# rev_p_v17.net
KiCad netlist of a schematic drawn in EAGLE
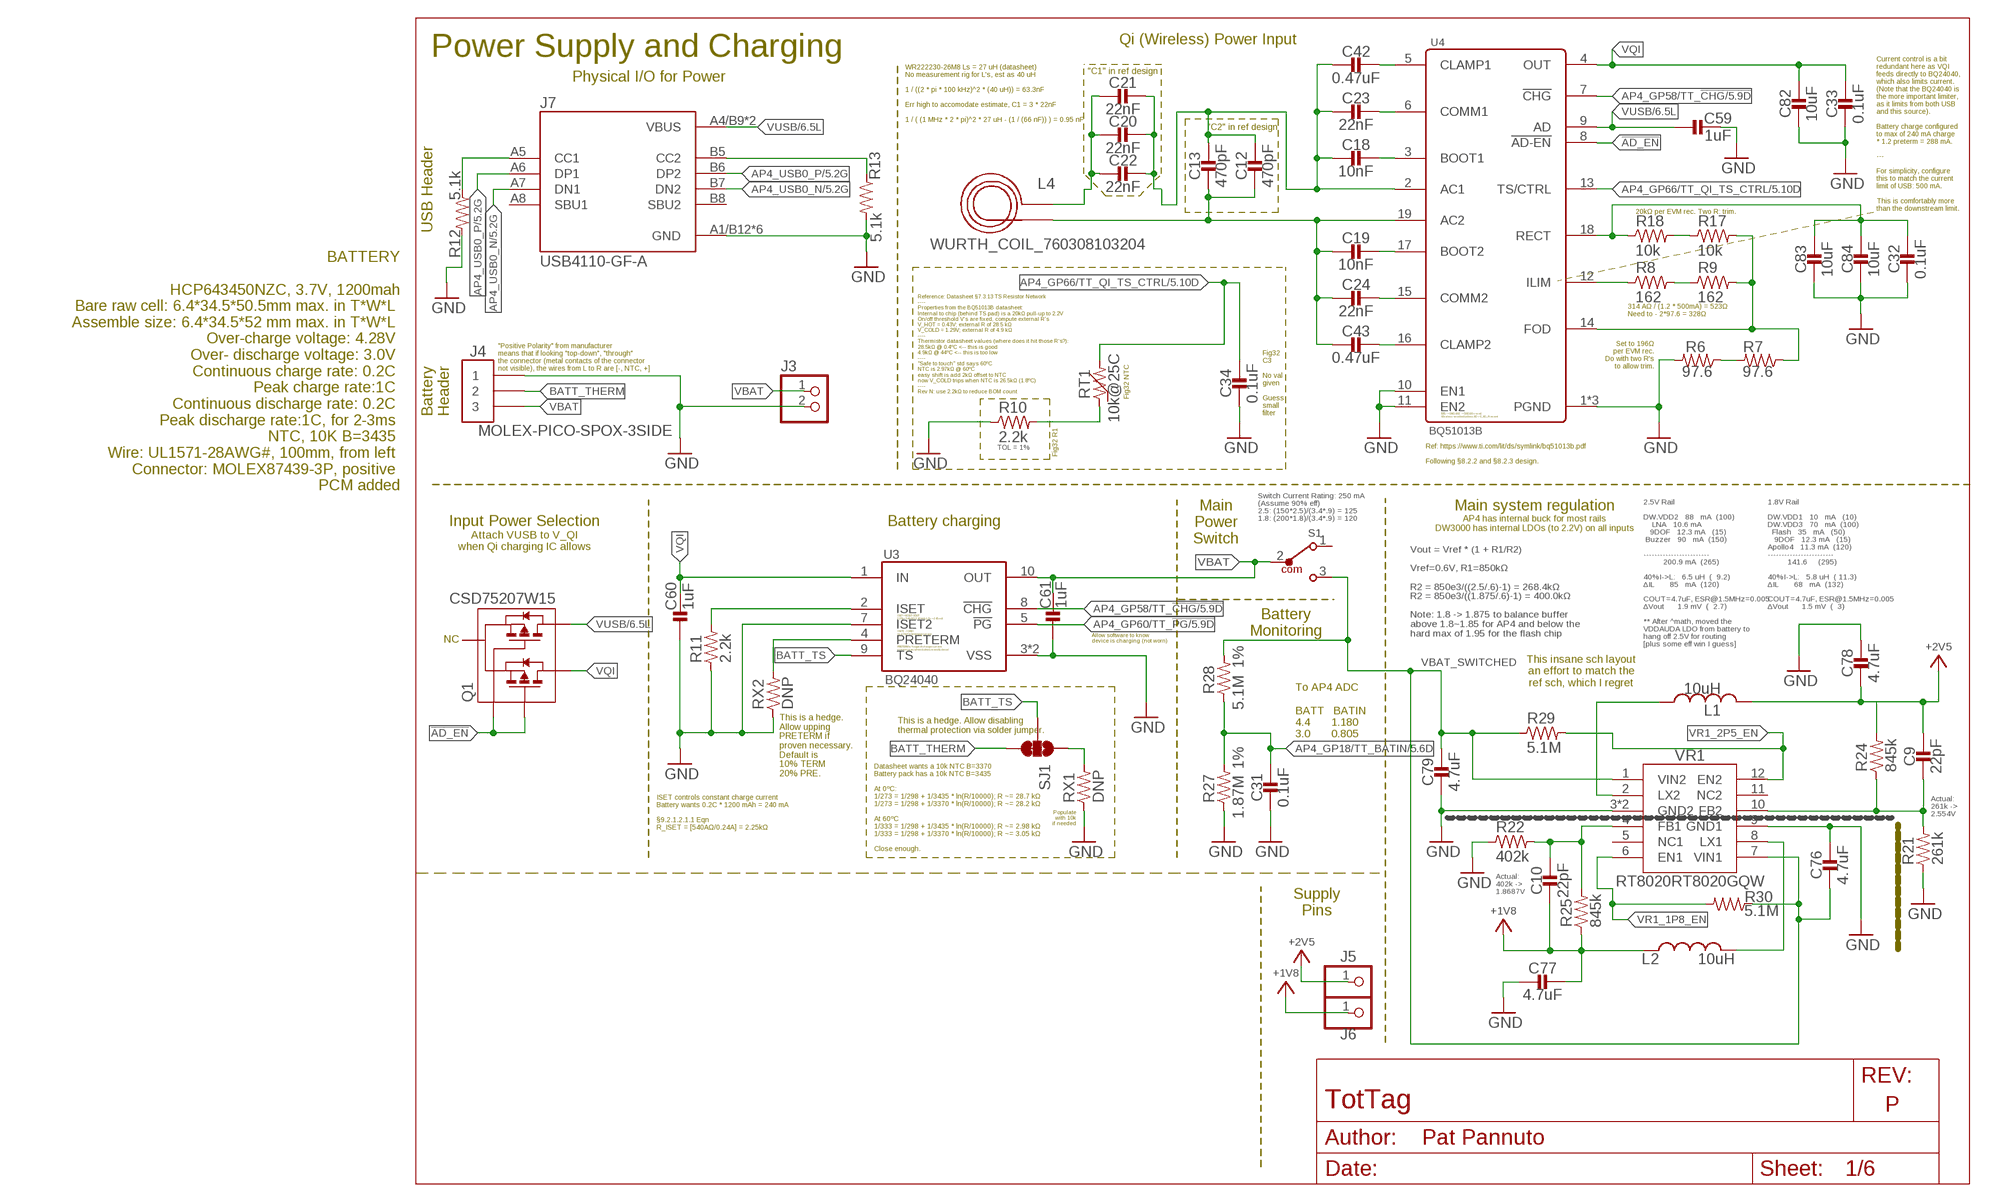
[diagram p0: schematic, sheet 1]
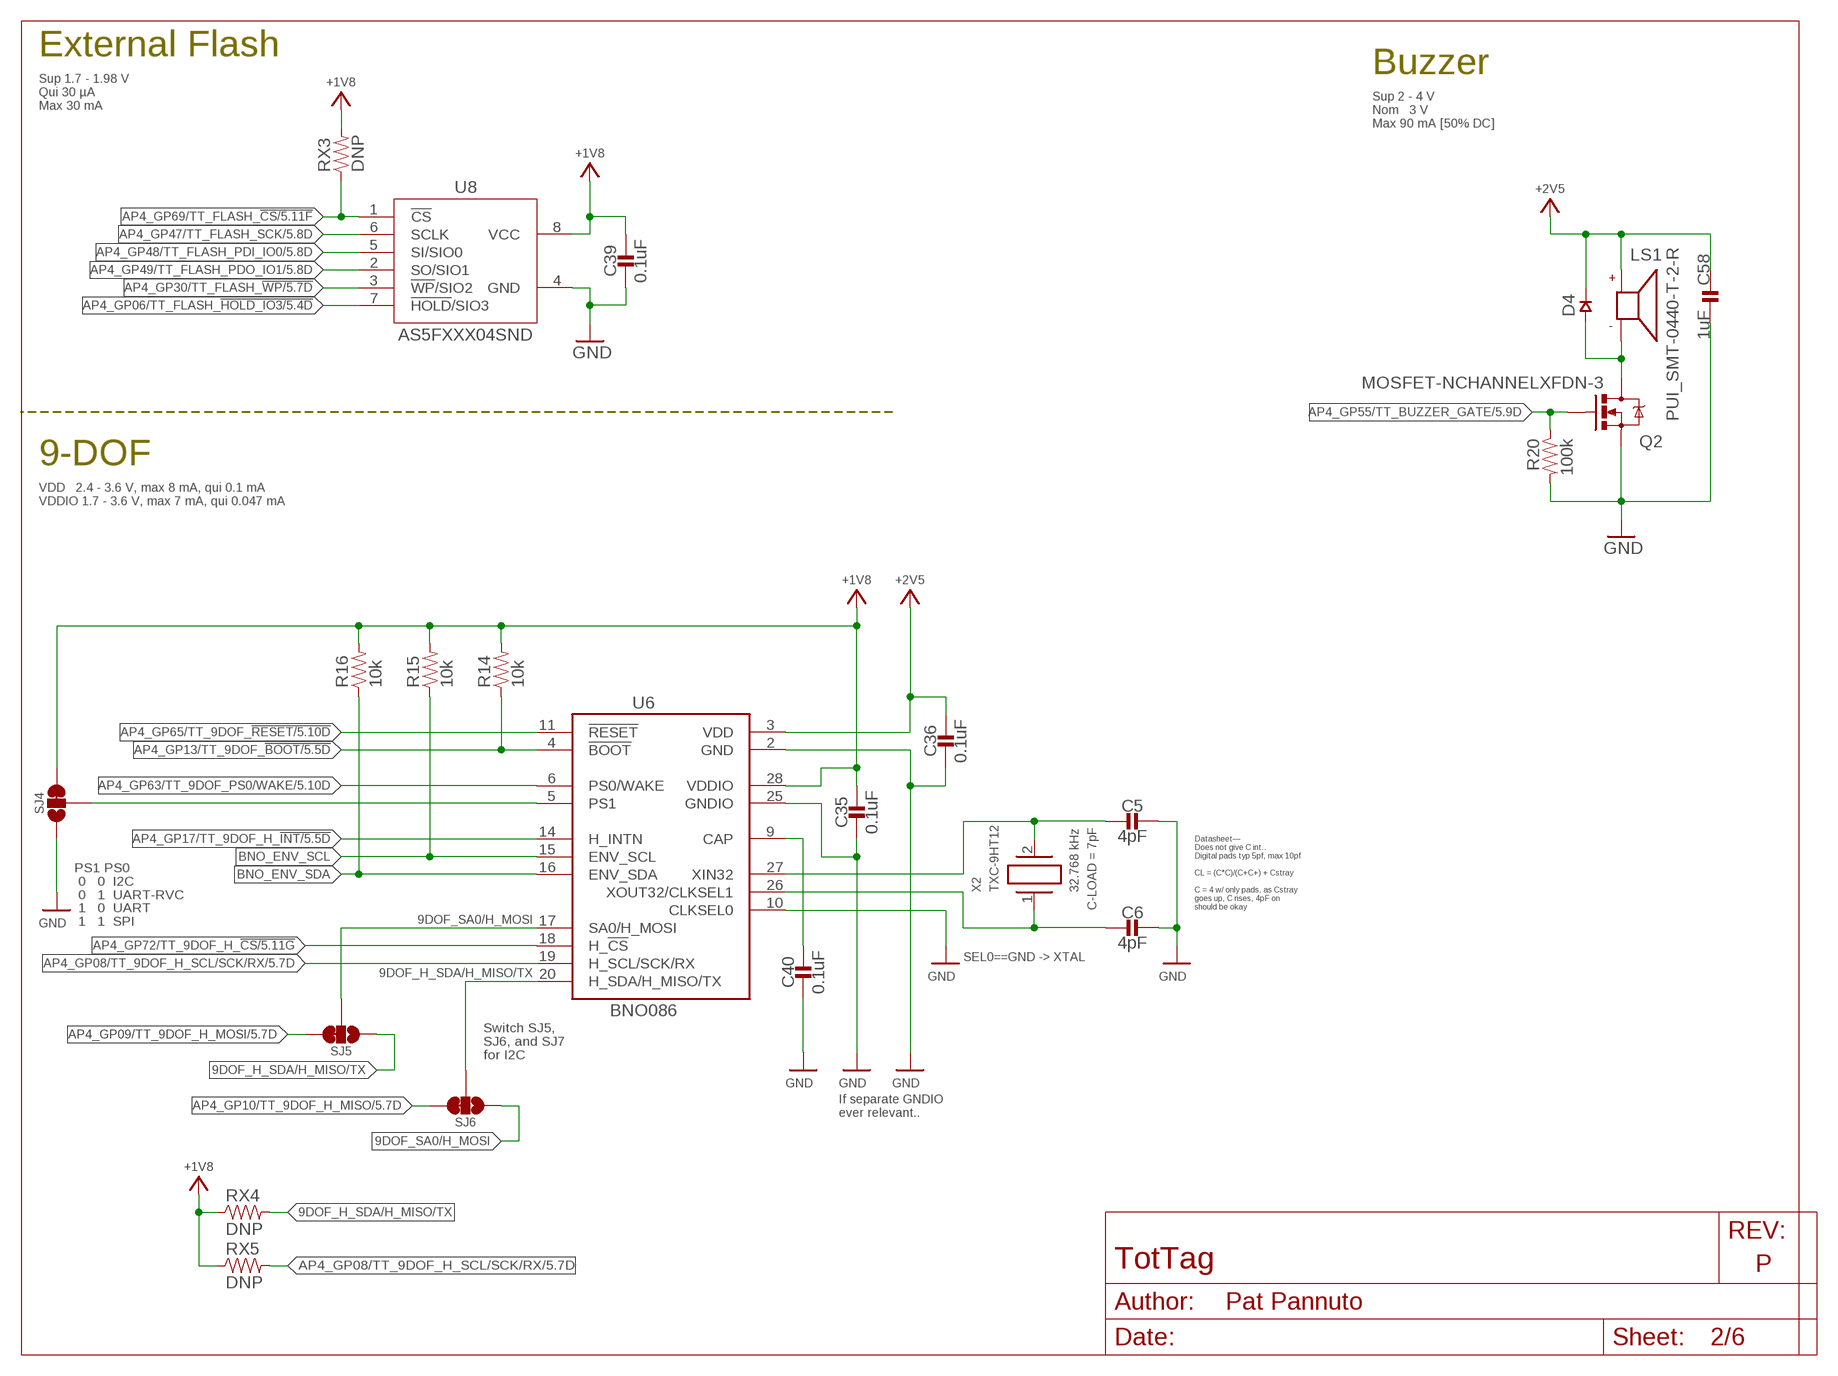
[diagram p1: schematic, sheet 2]
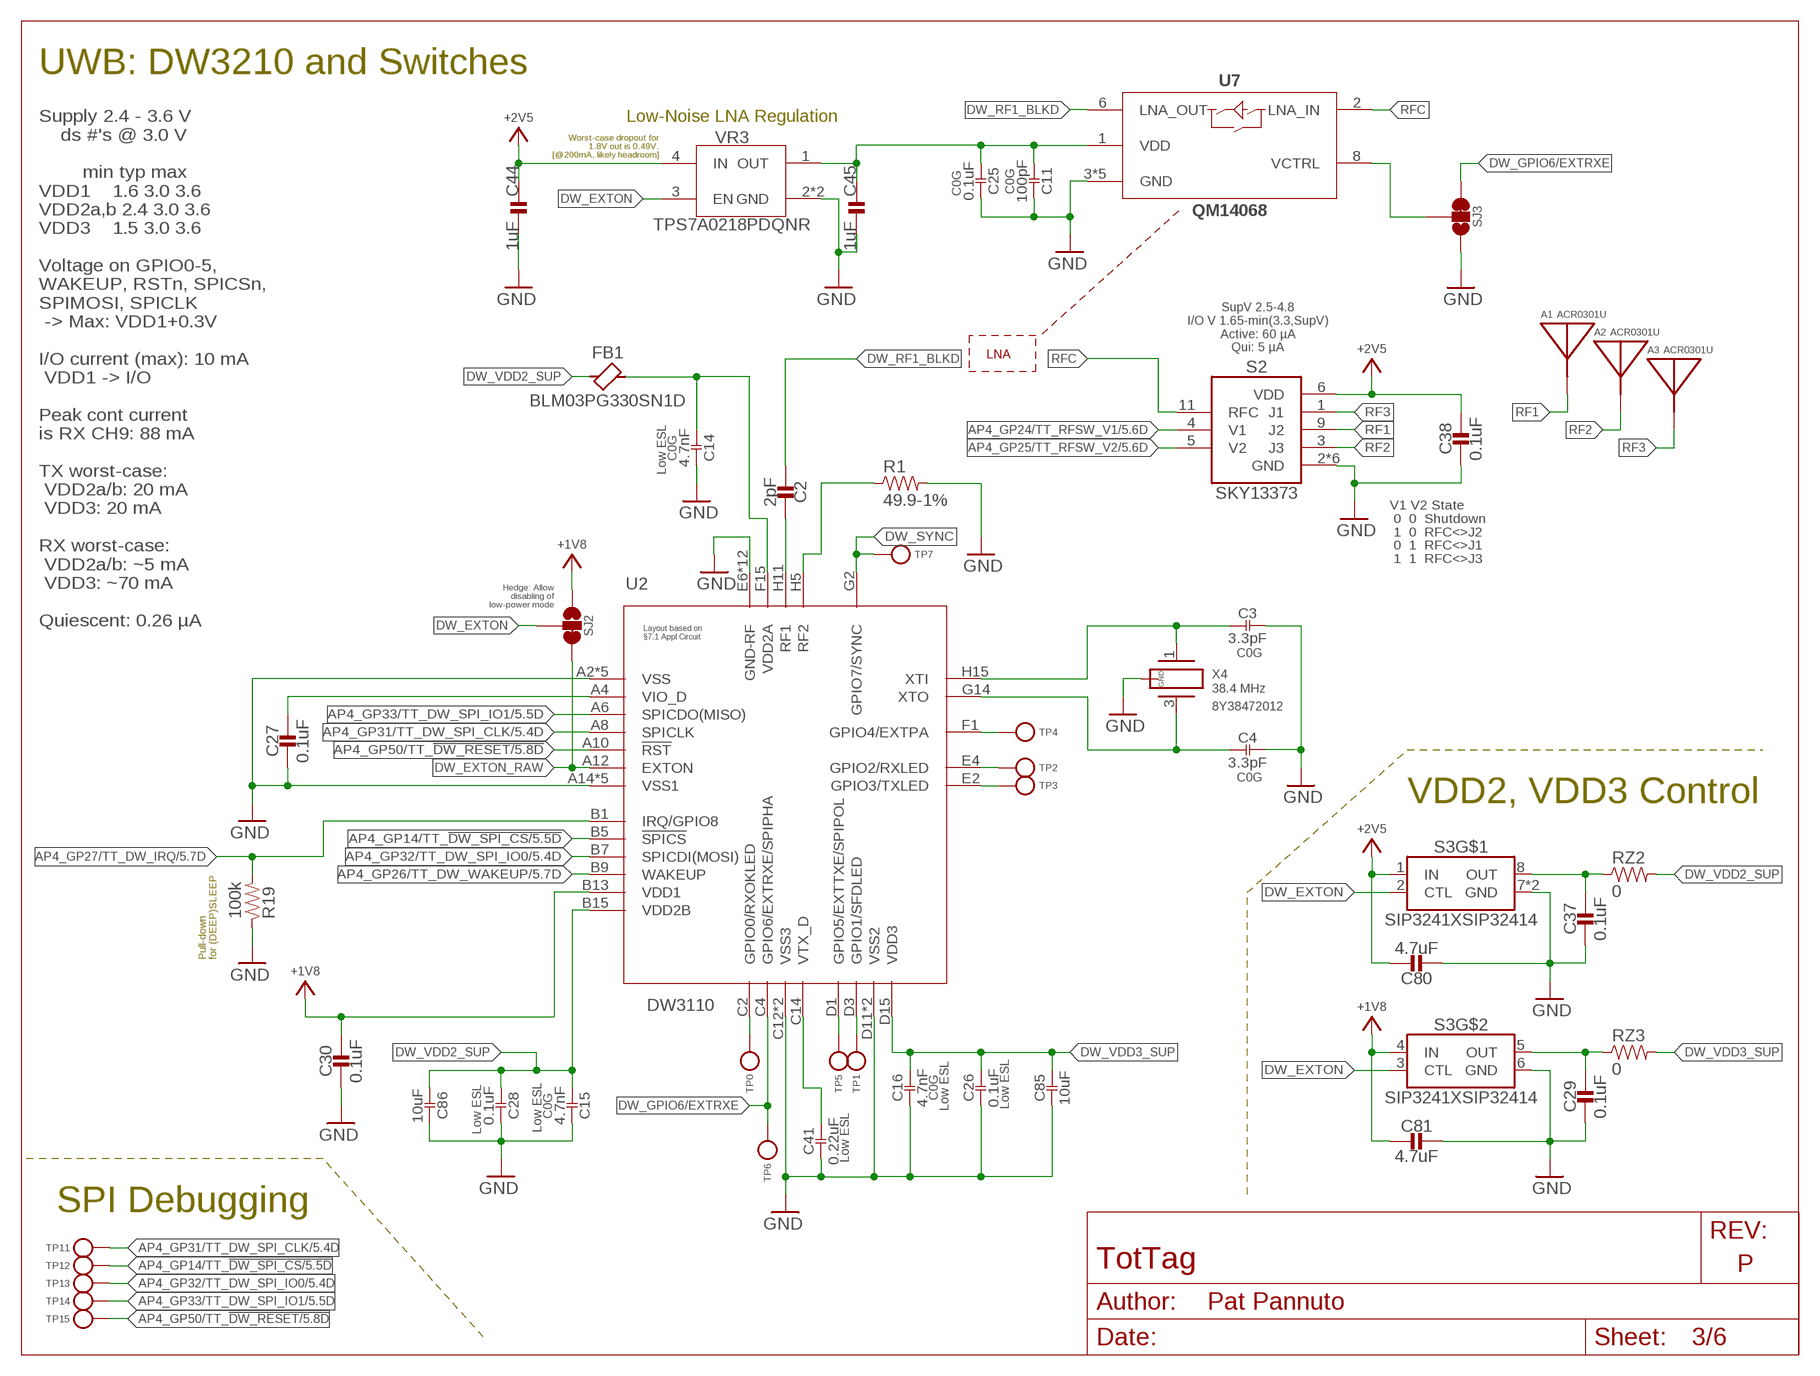
[diagram p2: schematic, sheet 3]
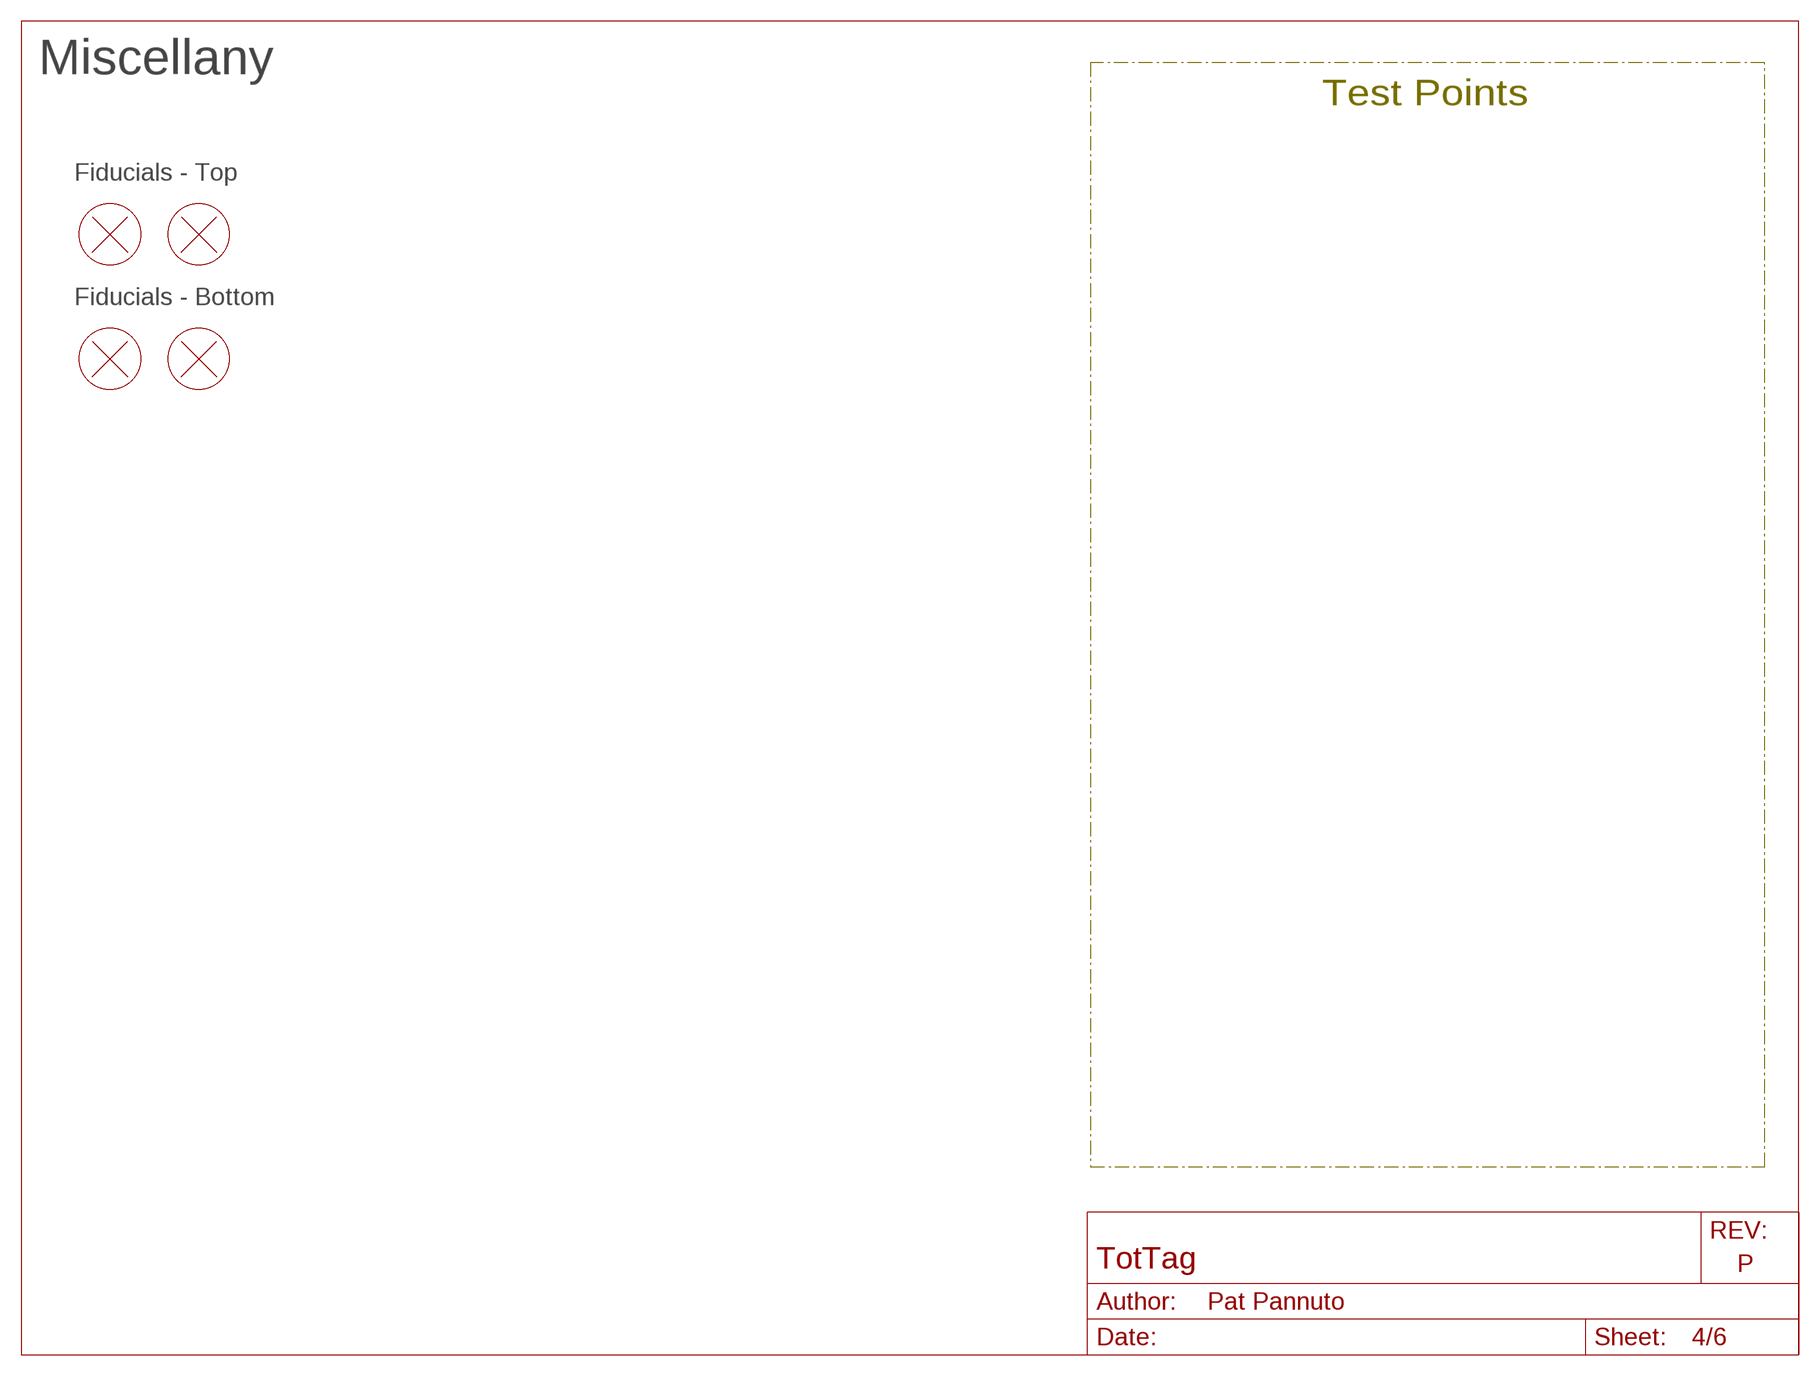
[diagram p3: schematic, sheet 4]
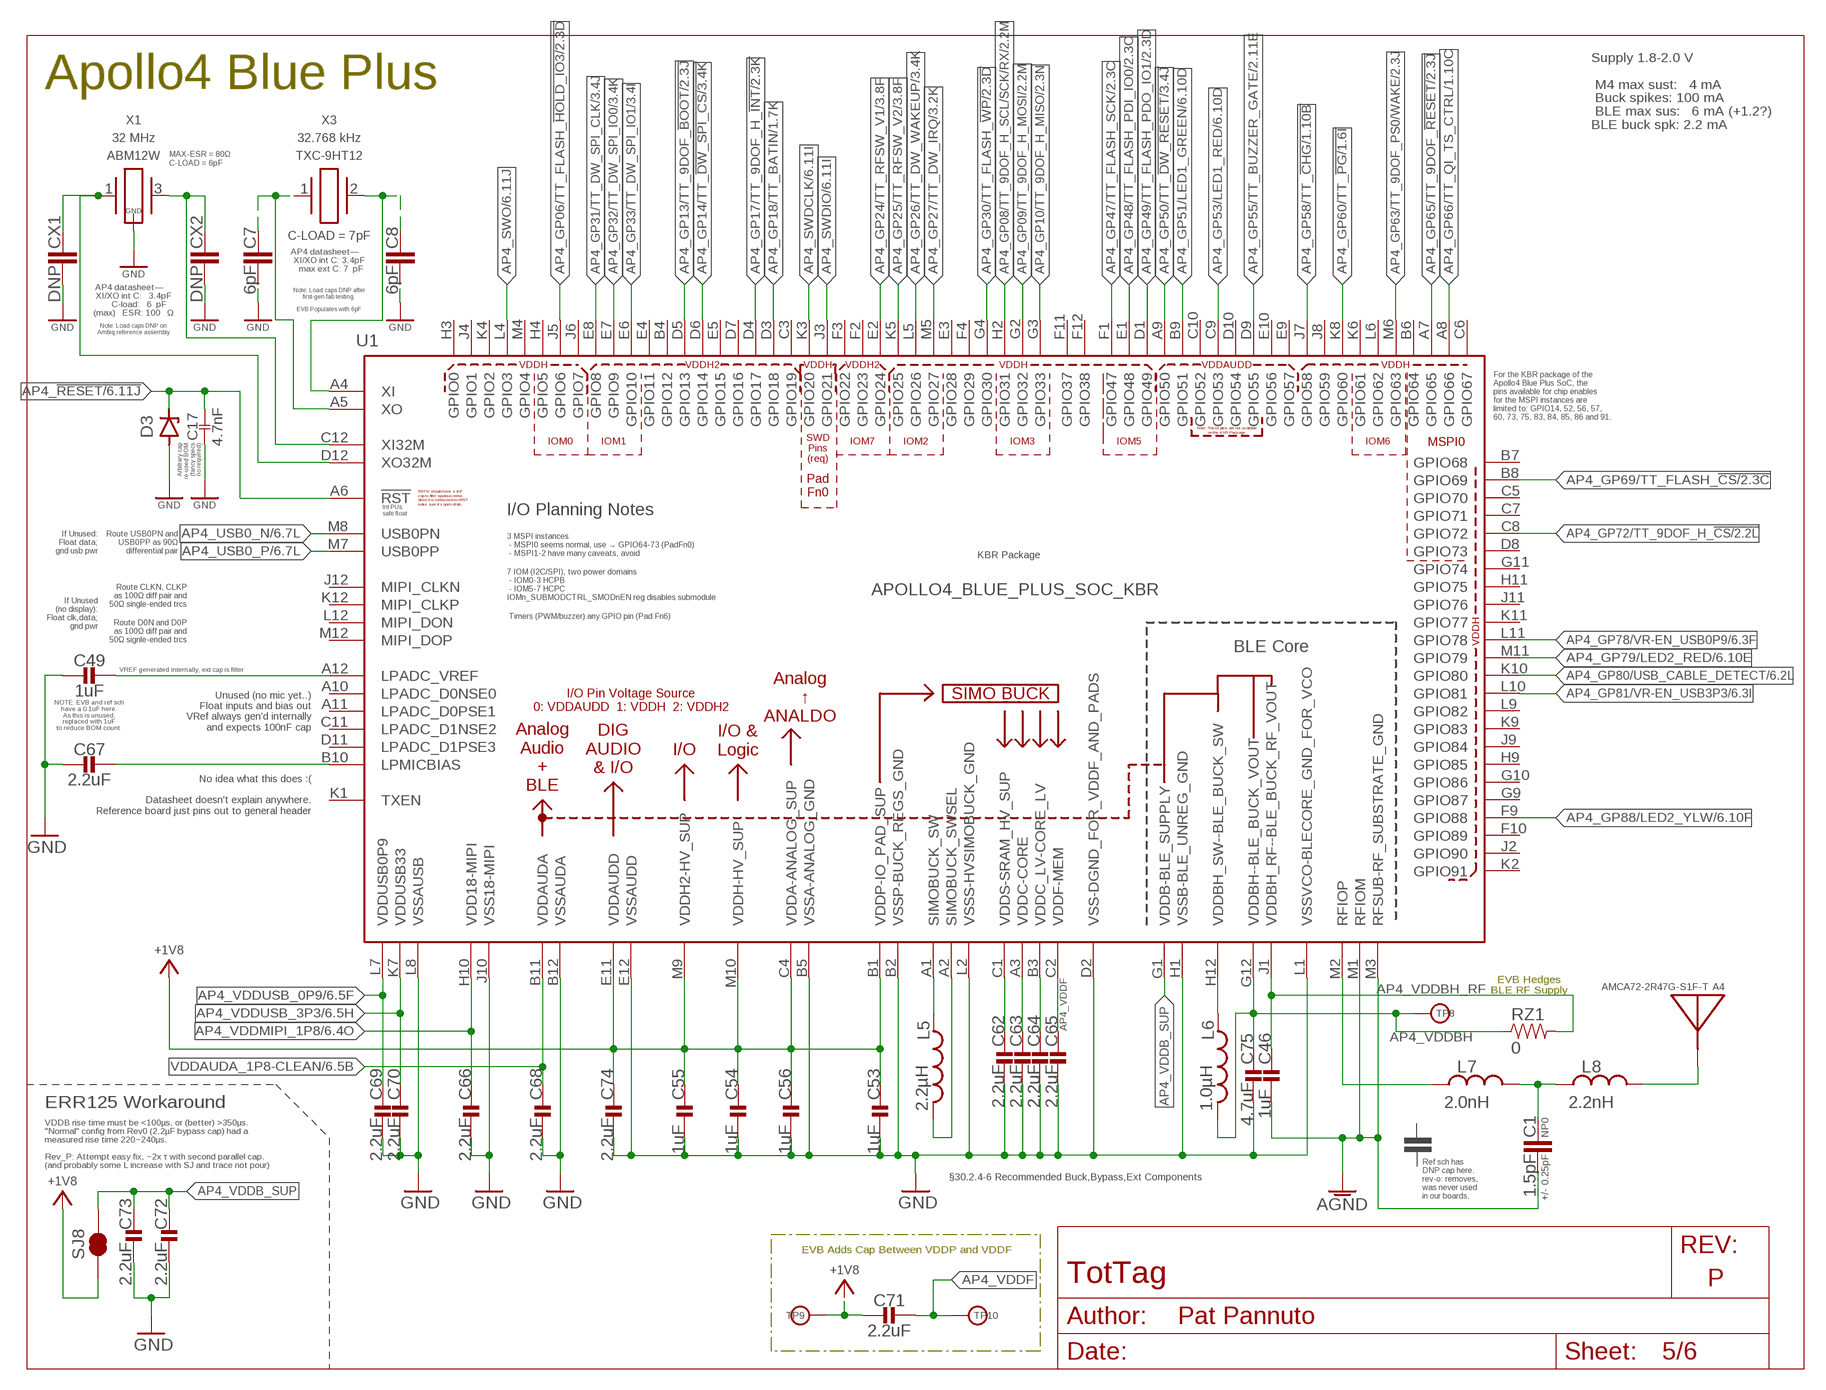
[diagram p4: schematic, sheet 5]
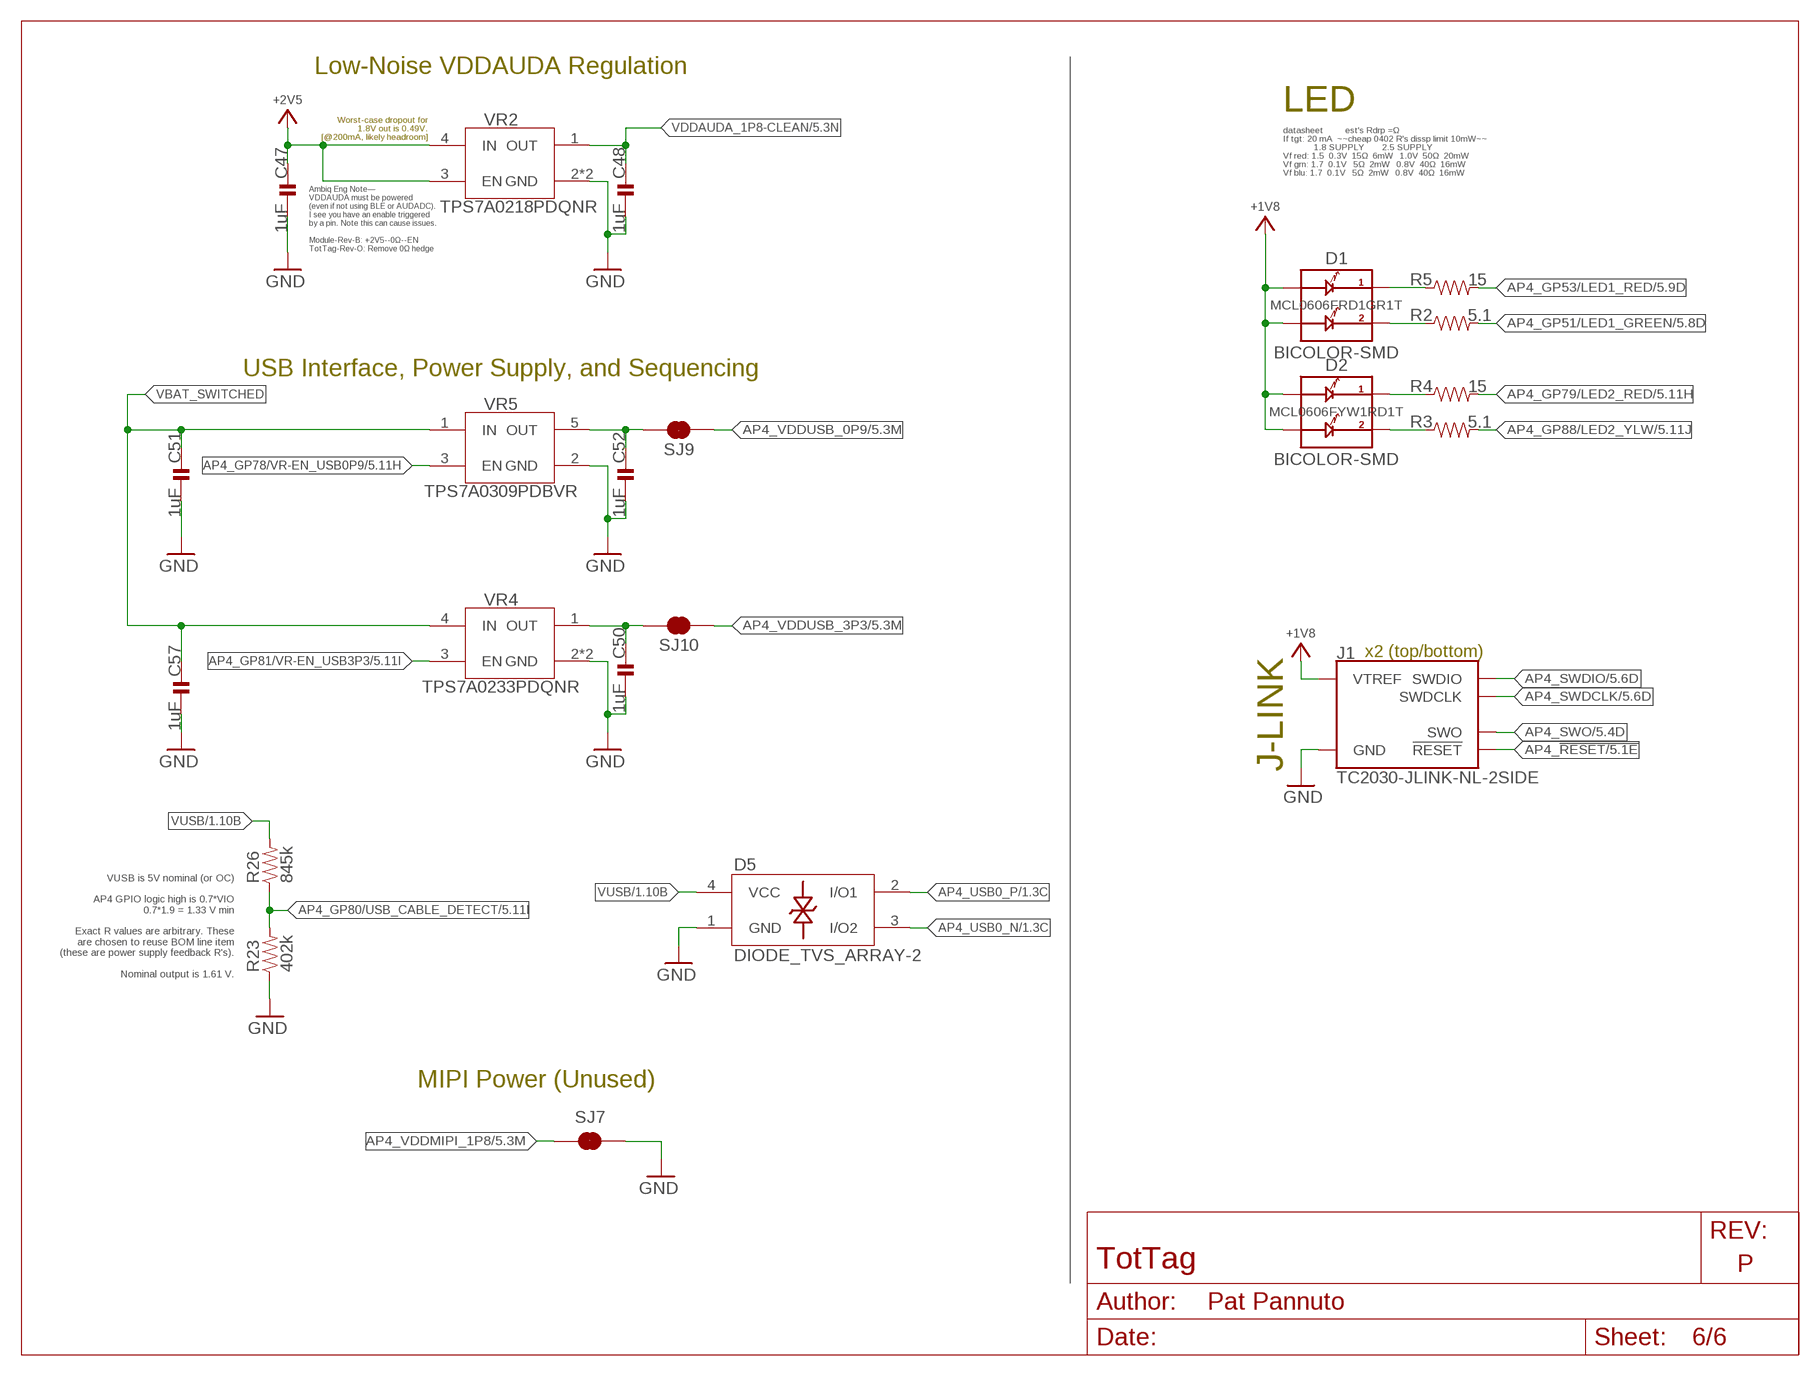
[diagram p5: schematic, sheet 6]

(export (version "E")
  (design (tool "Eeschema 10.0.6"))
  (components
    (comp (ref "FD1")
      (value "FIDUCIAL")
      (footprint "eagle-import:FIDUCIAL_1MM-CU_2MM-MASK")
      (libsource (lib "eagle-import") (part "FIDUCIAL"))
    )
    (comp (ref "FD2")
      (value "FIDUCIAL")
      (footprint "eagle-import:FIDUCIAL_1MM-CU_2MM-MASK")
      (libsource (lib "eagle-import") (part "FIDUCIAL"))
    )
    (comp (ref "FD3")
      (value "FIDUCIAL")
      (footprint "eagle-import:FIDUCIAL_1MM-CU_2MM-MASK")
      (libsource (lib "eagle-import") (part "FIDUCIAL"))
    )
    (comp (ref "FD4")
      (value "FIDUCIAL")
      (footprint "eagle-import:FIDUCIAL_1MM-CU_2MM-MASK")
      (libsource (lib "eagle-import") (part "FIDUCIAL"))
    )
    (comp (ref "A4")
      (value "AMCA72-2R47G-S1F-T")
      (footprint "eagle-import:AMCA72-2R470G-S1F-T")
      (fields (field (name "MPN") "AMCA72-2R470G-S1F-T4"))
      (libsource (lib "eagle-import") (part "AMCA72-2R47G-S1F-T"))
    )
    (comp (ref "C1")
      (value "1.5pF")
      (footprint "eagle-import:CAPC1005X60")
      (description "CAP CER 1.5PF 50V C0G/NP0 0402")
      (fields
        (field (name "MANUFACTURER") "KEMET")
        (field (name "MPN") "C0402C159C5GACTU")
        (field (name "TEMPCOEFF") "NP0")
        (field (name "TOLERANCE") "+/- 0.25pF")
      )
      (libsource (lib "eagle-import") (part "CCHIP-0402(1005-METRIC)_"))
    )
    (comp (ref "C7")
      (value "6pF")
      (footprint "eagle-import:CAPC1005X60")
      (fields (field (name "MANUFACTURER") "Murata") (field (name "MPN") "GCM1555C1H6R0BA16D"))
      (libsource (lib "eagle-import") (part "CCHIP-0402(1005-METRIC)_"))
    )
    (comp (ref "C8")
      (value "6pF")
      (footprint "eagle-import:CAPC1005X60")
      (fields (field (name "MANUFACTURER") "Murata") (field (name "MPN") "GCM1555C1H6R0BA16D"))
      (libsource (lib "eagle-import") (part "CCHIP-0402(1005-METRIC)_"))
    )
    (comp (ref "C17")
      (value "4.7nF")
      (footprint "eagle-import:SMD_1608M-0603US-C")
      (fields
        (field (name "EIA") "C0G")
        (field (name "FEATURES") "Low ESL")
        (field (name "MANUFACTURER") "KEMET")
        (field (name "MPN") "C0603C472J5GACTU")
      )
      (libsource (lib "eagle-import") (part "C0603US"))
    )
    (comp (ref "C46")
      (value "1uF")
      (footprint "eagle-import:0201_CAP")
      (fields (field (name "MANUFACTURER") "Murata") (field (name "MPN") "GRM033R61A105ME44D"))
      (libsource (lib "eagle-import") (part "passives_20904581_CAPACITOR0201_CAP"))
    )
    (comp (ref "C49")
      (value "1uF")
      (footprint "eagle-import:0201_CAP")
      (fields (field (name "MANUFACTURER") "MURATA") (field (name "MPN") "GRM033R61A105ME44D"))
      (libsource (lib "eagle-import") (part "passives_20904581_CAPACITOR0201_CAP"))
    )
    (comp (ref "C53")
      (value "1uF")
      (footprint "eagle-import:0201_CAP")
      (fields (field (name "MANUFACTURER") "Murata") (field (name "MPN") "GRM033R61A105ME44D"))
      (libsource (lib "eagle-import") (part "passives_20904581_CAPACITOR0201_CAP"))
    )
    (comp (ref "C54")
      (value "1uF")
      (footprint "eagle-import:0201_CAP")
      (fields (field (name "MANUFACTURER") "Murata") (field (name "MPN") "GRM033R61A105ME44D"))
      (libsource (lib "eagle-import") (part "passives_20904581_CAPACITOR0201_CAP"))
    )
    (comp (ref "C55")
      (value "1uF")
      (footprint "eagle-import:0201_CAP")
      (fields (field (name "MANUFACTURER") "Murata") (field (name "MPN") "GRM033R61A105ME44D"))
      (libsource (lib "eagle-import") (part "passives_20904581_CAPACITOR0201_CAP"))
    )
    (comp (ref "C56")
      (value "1uF")
      (footprint "eagle-import:0201_CAP")
      (fields (field (name "MANUFACTURER") "Murata") (field (name "MPN") "GRM033R61A105ME44D"))
      (libsource (lib "eagle-import") (part "passives_20904581_CAPACITOR0201_CAP"))
    )
    (comp (ref "C62")
      (value "2.2uF")
      (footprint "eagle-import:0201_CAP")
      (fields (field (name "MANUFACTURER") "Murata") (field (name "MPN") "GRM033R61A225KE47D"))
      (libsource (lib "eagle-import") (part "passives_20904581_CAPACITOR0201_CAP"))
    )
    (comp (ref "C63")
      (value "2.2uF")
      (footprint "eagle-import:0201_CAP")
      (fields (field (name "MANUFACTURER") "Murata") (field (name "MPN") "GRM033R61A225KE47D"))
      (libsource (lib "eagle-import") (part "passives_20904581_CAPACITOR0201_CAP"))
    )
    (comp (ref "C64")
      (value "2.2uF")
      (footprint "eagle-import:0201_CAP")
      (fields (field (name "MANUFACTURER") "Murata") (field (name "MPN") "GRM033R61A225KE47D"))
      (libsource (lib "eagle-import") (part "passives_20904581_CAPACITOR0201_CAP"))
    )
    (comp (ref "C65")
      (value "2.2uF")
      (footprint "eagle-import:0201_CAP")
      (fields (field (name "MANUFACTURER") "Murata") (field (name "MPN") "GRM033R61A225KE47D"))
      (libsource (lib "eagle-import") (part "passives_20904581_CAPACITOR0201_CAP"))
    )
    (comp (ref "C66")
      (value "2.2uF")
      (footprint "eagle-import:0201_CAP")
      (fields (field (name "MANUFACTURER") "Murata") (field (name "MPN") "GRM033R61A225KE47D"))
      (libsource (lib "eagle-import") (part "passives_20904581_CAPACITOR0201_CAP"))
    )
    (comp (ref "C67")
      (value "2.2uF")
      (footprint "eagle-import:0201_CAP")
      (fields (field (name "MANUFACTURER") "Murata") (field (name "MPN") "GRM033R61A225KE47D"))
      (libsource (lib "eagle-import") (part "passives_20904581_CAPACITOR0201_CAP"))
    )
    (comp (ref "C68")
      (value "2.2uF")
      (footprint "eagle-import:0201_CAP")
      (fields (field (name "MANUFACTURER") "Murata") (field (name "MPN") "GRM033R61A225KE47D"))
      (libsource (lib "eagle-import") (part "passives_20904581_CAPACITOR0201_CAP"))
    )
    (comp (ref "C69")
      (value "2.2uF")
      (footprint "eagle-import:0201_CAP")
      (fields (field (name "MANUFACTURER") "Murata") (field (name "MPN") "GRM033R61A225KE47D"))
      (libsource (lib "eagle-import") (part "passives_20904581_CAPACITOR0201_CAP"))
    )
    (comp (ref "C70")
      (value "2.2uF")
      (footprint "eagle-import:0201_CAP")
      (fields (field (name "MANUFACTURER") "Murata") (field (name "MPN") "GRM033R61A225KE47D"))
      (libsource (lib "eagle-import") (part "passives_20904581_CAPACITOR0201_CAP"))
    )
    (comp (ref "C71")
      (value "2.2uF")
      (footprint "eagle-import:0201_CAP")
      (fields (field (name "MANUFACTURER") "Murata") (field (name "MPN") "GRM033R61A225KE47D"))
      (libsource (lib "eagle-import") (part "passives_20904581_CAPACITOR0201_CAP"))
    )
    (comp (ref "C72")
      (value "2.2uF")
      (footprint "eagle-import:0201_CAP")
      (fields (field (name "MANUFACTURER") "Murata") (field (name "MPN") "GRM033R61A225KE47D"))
      (libsource (lib "eagle-import") (part "passives_20904581_CAPACITOR0201_CAP"))
    )
    (comp (ref "C73")
      (value "2.2uF")
      (footprint "eagle-import:0201_CAP")
      (fields (field (name "MANUFACTURER") "Murata") (field (name "MPN") "GRM033R61A225KE47D"))
      (libsource (lib "eagle-import") (part "passives_20904581_CAPACITOR0201_CAP"))
    )
    (comp (ref "C74")
      (value "2.2uF")
      (footprint "eagle-import:0201_CAP")
      (fields (field (name "MANUFACTURER") "Murata") (field (name "MPN") "GRM033R61A225KE47D"))
      (libsource (lib "eagle-import") (part "passives_20904581_CAPACITOR0201_CAP"))
    )
    (comp (ref "C75")
      (value "4.7uF")
      (footprint "eagle-import:0402_CAP")
      (fields (field (name "MPN") "CL05A475MP5NRNC"))
      (libsource (lib "eagle-import") (part "CAPACITOR0402_CAP"))
    )
    (comp (ref "CX1")
      (value "DNP")
      (footprint "eagle-import:CAPC1005X60")
      (libsource (lib "eagle-import") (part "CCHIP-0402(1005-METRIC)_"))
    )
    (comp (ref "CX2")
      (value "DNP")
      (footprint "eagle-import:CAPC1005X60")
      (libsource (lib "eagle-import") (part "CCHIP-0402(1005-METRIC)_"))
    )
    (comp (ref "D3")
      (value "ZENER")
      (footprint "eagle-import:SODFL1608X70")
      (description "DIODE TVS 5.5V STANDOFF 8V BREAKDOWN SC79")
      (fields (field (name "MANUFACTURER") "NXP SEMICONDUCTOR") (field (name "MPN") "PESD5V0X1UB,135"))
      (libsource (lib "eagle-import") (part "ZENERSODFL(1608-METRIC)_"))
    )
    (comp (ref "L5")
      (value "2.2µH")
      (footprint "eagle-import:0805_CAP")
      (fields (field (name "MANUFACTURER") "Murata") (field (name "MPN") "DFE201210U-2R2M=P2"))
      (libsource (lib "eagle-import") (part "INDUCTOR0805"))
    )
    (comp (ref "L6")
      (value "1.0µH")
      (footprint "eagle-import:0603_CAP")
      (fields (field (name "MANUFACTURER") "Taiyo Yuden") (field (name "MPN") "MCKK1608T1R0MN"))
      (libsource (lib "eagle-import") (part "INDUCTOR0603"))
    )
    (comp (ref "L7")
      (value "2.0nH")
      (footprint "eagle-import:INDC1006X60N")
      (description "FIXED IND 2.0NH0.1NH SMD")
      (fields
        (field (name "MANUFACTURER") "Murata")
        (field (name "MPN") "LQG15HS2N0B02D")
        (field (name "TOLERANCE") "+/- 0.1 nH")
      )
      (libsource (lib "eagle-import") (part "LCHIP-0402(1006-METRIC)_"))
    )
    (comp (ref "L8")
      (value "2.2nH")
      (footprint "eagle-import:INDC1006X60N")
      (description "FIXED IND 2.2NH0.1NH SMD")
      (fields
        (field (name "MANUFACTURER") "Murata")
        (field (name "MPN") "LQG15HN2N2B02D")
        (field (name "TOLERANCE") "+/- 0.1 nH")
      )
      (libsource (lib "eagle-import") (part "LCHIP-0402(1006-METRIC)_"))
    )
    (comp (ref "RZ1")
      (value "0")
      (footprint "eagle-import:0402_RES")
      (fields (field (name "MPN") "RMCF0402ZT0R00"))
      (libsource (lib "eagle-import") (part "passives_20904581_RESISTOR0402_RES"))
    )
    (comp (ref "SJ8")
      (value "JUMPER-SMT_2_NC_TRACE_SILK")
      (footprint "eagle-import:SMT-JUMPER_2_NC_TRACE_SILK")
      (libsource (lib "eagle-import") (part "JUMPER-SMT_2_NC_TRACE_SILK"))
    )
    (comp (ref "TP8")
      (value "TEST-POINT")
      (footprint "eagle-import:PAD.03X.03")
      (libsource (lib "eagle-import") (part "TEST-POINT"))
    )
    (comp (ref "TP9")
      (value "TEST-POINT")
      (footprint "eagle-import:PAD.03X.03")
      (libsource (lib "eagle-import") (part "TEST-POINT"))
    )
    (comp (ref "TP10")
      (value "TEST-POINT")
      (footprint "eagle-import:PAD.03X.03")
      (libsource (lib "eagle-import") (part "TEST-POINT"))
    )
    (comp (ref "U1")
      (value "APOLLO4_BLUE_PLUS_SOC_KBR")
      (footprint "eagle-import:APOLLO4_BLUE_SOC_BGA")
      (fields (field (name "MANUFACTURER") "Ambiq") (field (name "MPN") "AMA4B2KP-KBR"))
      (libsource (lib "eagle-import") (part "APOLLO4_BLUE_PLUS_SOC_KBR"))
    )
    (comp (ref "X1")
      (value "ABM12W")
      (footprint "eagle-import:ABM12W")
      (fields
        (field (name "C-LOAD") "6pF")
        (field (name "FREQUENCY") "32 MHz")
        (field (name "MANUFACTURER") "Abracon")
        (field (name "MAX-ESR") "80Ω")
        (field (name "MPN") "ABM12W-32.0000MHZ-6-D1X-T3")
      )
      (libsource (lib "eagle-import") (part "ABM12W"))
    )
    (comp (ref "X3")
      (value "TXC-9HT12")
      (footprint "eagle-import:TXC-9HT12")
      (fields
        (field (name "C-LOAD") "7pF")
        (field (name "FREQUENCY") "32.768 kHz")
        (field (name "MANUFACTURER") "TXC Corp")
        (field (name "MPN") "9HT12-32.768KDZY-T")
      )
      (libsource (lib "eagle-import") (part "TXC-9HT12"))
    )
    (comp (ref "C5")
      (value "4pF")
      (footprint "eagle-import:0201_CAP")
      (fields (field (name "MANUFACTURER") "Murata") (field (name "MPN") "GRM0335C1H4R0BA01D"))
      (libsource (lib "eagle-import") (part "passives_20904581_CAPACITOR0201_CAP"))
    )
    (comp (ref "C6")
      (value "4pF")
      (footprint "eagle-import:0201_CAP")
      (fields (field (name "MANUFACTURER") "Murata") (field (name "MPN") "GRM0335C1H4R0BA01D"))
      (libsource (lib "eagle-import") (part "passives_20904581_CAPACITOR0201_CAP"))
    )
    (comp (ref "C35")
      (value "0.1uF")
      (footprint "eagle-import:0402_CAP")
      (fields (field (name "MPN") "CL05A104KP5NNNC"))
      (libsource (lib "eagle-import") (part "passives_20904581_CAPACITOR0402_CAP"))
    )
    (comp (ref "C36")
      (value "0.1uF")
      (footprint "eagle-import:0402_CAP")
      (fields (field (name "MPN") "CL05A104KP5NNNC"))
      (libsource (lib "eagle-import") (part "passives_20904581_CAPACITOR0402_CAP"))
    )
    (comp (ref "C39")
      (value "0.1uF")
      (footprint "eagle-import:0402_CAP")
      (fields (field (name "MPN") "CL05A104KP5NNNC"))
      (libsource (lib "eagle-import") (part "passives_20904581_CAPACITOR0402_CAP"))
    )
    (comp (ref "C40")
      (value "0.1uF")
      (footprint "eagle-import:0402_CAP")
      (fields (field (name "MPN") "CL05A104KP5NNNC"))
      (libsource (lib "eagle-import") (part "CAPACITOR0402_CAP"))
    )
    (comp (ref "C58")
      (value "1uF")
      (footprint "eagle-import:0201_CAP")
      (fields (field (name "MANUFACTURER") "Murata") (field (name "MPN") "GRM033R61A105ME44D"))
      (libsource (lib "eagle-import") (part "passives_20904581_CAPACITOR0201_CAP"))
    )
    (comp (ref "D4")
      (value "DIODE0402")
      (footprint "eagle-import:0402_DIODE")
      (fields (field (name "MPN") "CDSQR400B-HF"))
      (libsource (lib "eagle-import") (part "DIODE0402"))
    )
    (comp (ref "LS1")
      (value "PUI_SMT-0440-T-2-R")
      (footprint "eagle-import:SMT-0440-T-2-R")
      (fields (field (name "MPN") "SMT-0440-T-2-R"))
      (libsource (lib "eagle-import") (part "PUI_SMT-0440-T-2-R"))
    )
    (comp (ref "Q2")
      (value "MOSFET-NCHANNELXFDN-3")
      (footprint "eagle-import:XFDFN-3")
      (libsource (lib "eagle-import") (part "MOSFET-NCHANNELXFDN-3"))
    )
    (comp (ref "R14")
      (value "10k")
      (footprint "eagle-import:0402_RES")
      (fields (field (name "MPN") "RC0402JR-0710KL"))
      (libsource (lib "eagle-import") (part "RESISTOR0402_RES"))
    )
    (comp (ref "R15")
      (value "10k")
      (footprint "eagle-import:0402_RES")
      (fields (field (name "MPN") "RC0402JR-0710KL"))
      (libsource (lib "eagle-import") (part "RESISTOR0402_RES"))
    )
    (comp (ref "R16")
      (value "10k")
      (footprint "eagle-import:0402_RES")
      (fields (field (name "MPN") "RC0402JR-0710KL"))
      (libsource (lib "eagle-import") (part "RESISTOR0402_RES"))
    )
    (comp (ref "R20")
      (value "100k")
      (footprint "eagle-import:0402_RES")
      (fields (field (name "MPN") "RT0402BRE07100KL"))
      (libsource (lib "eagle-import") (part "RESISTOR0402_RES"))
    )
    (comp (ref "RX3")
      (value "DNP")
      (footprint "eagle-import:0603-RES")
      (libsource (lib "eagle-import") (part "passives_20904581_RESISTOR0603_RES"))
    )
    (comp (ref "RX4")
      (value "DNP")
      (footprint "eagle-import:0603-RES")
      (libsource (lib "eagle-import") (part "passives_20904581_RESISTOR0603_RES"))
    )
    (comp (ref "RX5")
      (value "DNP")
      (footprint "eagle-import:0603-RES")
      (libsource (lib "eagle-import") (part "passives_20904581_RESISTOR0603_RES"))
    )
    (comp (ref "SJ4")
      (value "JUMPER-SMT_3_1-NC_TRACE_SILK")
      (footprint "eagle-import:SMT-JUMPER_3_1-NC_TRACE_SILK")
      (libsource (lib "eagle-import") (part "JUMPER-SMT_3_1-NC_TRACE_SILK"))
    )
    (comp (ref "SJ5")
      (value "JUMPER-SMT_3_1-NC_TRACE_SILK")
      (footprint "eagle-import:SMT-JUMPER_3_1-NC_TRACE_SILK")
      (libsource (lib "eagle-import") (part "JUMPER-SMT_3_1-NC_TRACE_SILK"))
    )
    (comp (ref "SJ6")
      (value "JUMPER-SMT_3_1-NC_TRACE_SILK")
      (footprint "eagle-import:SMT-JUMPER_3_1-NC_TRACE_SILK")
      (libsource (lib "eagle-import") (part "JUMPER-SMT_3_1-NC_TRACE_SILK"))
    )
    (comp (ref "U6")
      (value "BNO086")
      (footprint "eagle-import:LGA28R0P510X4_5P2X3P8X1")
      (fields (field (name "MANUFACTURER") "CEVA Technologies, Inc."))
      (libsource (lib "eagle-import") (part "BNO086"))
    )
    (comp (ref "U8")
      (value "AS5FXXX04SND")
      (footprint "eagle-import:AS5FXXXXXXXX-XXLXN")
      (fields (field (name "MANUFACTURER") "Alliance Memory") (field (name "MPN") "AS5F18G04SND-10LIN"))
      (libsource (lib "eagle-import") (part "AS5FXXX04SND"))
    )
    (comp (ref "X2")
      (value "TXC-9HT12")
      (footprint "eagle-import:TXC-9HT12")
      (fields
        (field (name "C-LOAD") "7pF")
        (field (name "FREQUENCY") "32.768 kHz")
        (field (name "MANUFACTURER") "TXC Corp")
        (field (name "MPN") "9HT12-32.768KDZY-T")
      )
      (libsource (lib "eagle-import") (part "TXC-9HT12"))
    )
    (comp (ref "A1")
      (value "ACR0301U")
      (footprint "eagle-import:ACR0301U")
      (fields (field (name "MANUFACTURER") "Abracon"))
      (libsource (lib "eagle-import") (part "ACR0301U"))
    )
    (comp (ref "A2")
      (value "ACR0301U")
      (footprint "eagle-import:ACR0301U")
      (fields (field (name "MANUFACTURER") "Abracon"))
      (libsource (lib "eagle-import") (part "ACR0301U"))
    )
    (comp (ref "A3")
      (value "ACR0301U")
      (footprint "eagle-import:ACR0301U")
      (fields (field (name "MANUFACTURER") "Abracon"))
      (libsource (lib "eagle-import") (part "ACR0301U"))
    )
    (comp (ref "C2")
      (value "2pF")
      (footprint "eagle-import:0201_CAP")
      (fields (field (name "MPN") "CBR02C209A5GAC"))
      (libsource (lib "eagle-import") (part "CAPACITOR0201_CAP"))
    )
    (comp (ref "C3")
      (value "3.3pF")
      (footprint "eagle-import:SMD_2012M-0805US-C")
      (fields
        (field (name "EIA") "C0G")
        (field (name "MANUFACTURER") "KYOCERA AVX")
        (field (name "MPN") "600F3R3BT250XT")
      )
      (libsource (lib "eagle-import") (part "C0805US"))
    )
    (comp (ref "C4")
      (value "3.3pF")
      (footprint "eagle-import:SMD_2012M-0805US-C")
      (fields
        (field (name "EIA") "C0G")
        (field (name "MANUFACTURER") "KYOCERA AVX")
        (field (name "MPN") "600F3R3BT250XT")
      )
      (libsource (lib "eagle-import") (part "C0805US"))
    )
    (comp (ref "C11")
      (value "100pF")
      (footprint "eagle-import:SMD_1005M-0402US-C")
      (fields (field (name "EIA") "C0G") (field (name "MPN") "C0402C101J3GACTU"))
      (libsource (lib "eagle-import") (part "C0402US"))
    )
    (comp (ref "C14")
      (value "4.7nF")
      (footprint "eagle-import:SMD_1608M-0603US-C")
      (fields
        (field (name "EIA") "C0G")
        (field (name "FEATURES") "Low ESL")
        (field (name "MANUFACTURER") "KEMET")
        (field (name "MPN") "C0603C472J5GACTU")
      )
      (libsource (lib "eagle-import") (part "C0603US"))
    )
    (comp (ref "C15")
      (value "4.7nF")
      (footprint "eagle-import:SMD_1608M-0603US-C")
      (fields
        (field (name "EIA") "C0G")
        (field (name "FEATURES") "Low ESL")
        (field (name "MANUFACTURER") "KEMET")
        (field (name "MPN") "C0603C472J5GACTU")
      )
      (libsource (lib "eagle-import") (part "C0603US"))
    )
    (comp (ref "C16")
      (value "4.7nF")
      (footprint "eagle-import:SMD_1608M-0603US-C")
      (fields
        (field (name "EIA") "C0G")
        (field (name "FEATURES") "Low ESL")
        (field (name "MANUFACTURER") "KEMET")
        (field (name "MPN") "C0603C472J5GACTU")
      )
      (libsource (lib "eagle-import") (part "C0603US"))
    )
    (comp (ref "C25")
      (value "0.1uF")
      (footprint "eagle-import:SMD_3216M-1206US-C")
      (fields (field (name "EIA") "C0G") (field (name "MPN") "GRM31C5C1H104JA01L"))
      (libsource (lib "eagle-import") (part "C1206US"))
    )
    (comp (ref "C26")
      (value "0.1uF")
      (footprint "eagle-import:SMD_1608M-0603US-C")
      (fields (field (name "FEATURES") "Low ESL") (field (name "MPN") "C1608X7R1H104K080AA"))
      (libsource (lib "eagle-import") (part "C0603US"))
    )
    (comp (ref "C27")
      (value "0.1uF")
      (footprint "eagle-import:0402_CAP")
      (fields (field (name "MPN") "CL05A104KP5NNNC"))
      (libsource (lib "eagle-import") (part "passives_20904581_CAPACITOR0402_CAP"))
    )
    (comp (ref "C28")
      (value "0.1uF")
      (footprint "eagle-import:SMD_1608M-0603US-C")
      (fields (field (name "FEATURES") "Low ESL") (field (name "MPN") "C1608X7R1H104K080AA"))
      (libsource (lib "eagle-import") (part "C0603US"))
    )
    (comp (ref "C29")
      (value "0.1uF")
      (footprint "eagle-import:0402_CAP")
      (fields (field (name "MPN") "CL05A104KP5NNNC"))
      (libsource (lib "eagle-import") (part "passives_20904581_CAPACITOR0402_CAP"))
    )
    (comp (ref "C30")
      (value "0.1uF")
      (footprint "eagle-import:0402_CAP")
      (fields (field (name "MPN") "CL05A104KP5NNNC"))
      (libsource (lib "eagle-import") (part "passives_20904581_CAPACITOR0402_CAP"))
    )
    (comp (ref "C37")
      (value "0.1uF")
      (footprint "eagle-import:0402_CAP")
      (fields (field (name "MPN") "CL05A104KP5NNNC"))
      (libsource (lib "eagle-import") (part "passives_20904581_CAPACITOR0402_CAP"))
    )
    (comp (ref "C38")
      (value "0.1uF")
      (footprint "eagle-import:0402_CAP")
      (fields (field (name "MPN") "CL05A104KP5NNNC"))
      (libsource (lib "eagle-import") (part "passives_20904581_CAPACITOR0402_CAP"))
    )
    (comp (ref "C41")
      (value "0.22uF")
      (footprint "eagle-import:SMD_1608M-0603US-C")
      (fields (field (name "FEATURES") "Low ESL") (field (name "MPN") "C1608X7R1H224K080AB"))
      (libsource (lib "eagle-import") (part "C0603US"))
    )
    (comp (ref "C44")
      (value "1uF")
      (footprint "eagle-import:0201_CAP")
      (fields (field (name "MANUFACTURER") "Murata") (field (name "MPN") "GRM033R61A105ME44D"))
      (libsource (lib "eagle-import") (part "passives_20904581_CAPACITOR0201_CAP"))
    )
    (comp (ref "C45")
      (value "1uF")
      (footprint "eagle-import:0201_CAP")
      (fields (field (name "MANUFACTURER") "Murata") (field (name "MPN") "GRM033R61A105ME44D"))
      (libsource (lib "eagle-import") (part "passives_20904581_CAPACITOR0201_CAP"))
    )
    (comp (ref "C80")
      (value "4.7uF")
      (footprint "eagle-import:0603_CAP")
      (fields (field (name "MPN") "C1608X7S1A475K080AC"))
      (libsource (lib "eagle-import") (part "passives_20904581_CAPACITOR0603_CAP"))
    )
    (comp (ref "C81")
      (value "4.7uF")
      (footprint "eagle-import:0603_CAP")
      (fields (field (name "MPN") "C1608X7S1A475K080AC"))
      (libsource (lib "eagle-import") (part "passives_20904581_CAPACITOR0603_CAP"))
    )
    (comp (ref "C85")
      (value "10uF")
      (footprint "eagle-import:SMD_1608M-0603US-C")
      (fields (field (name "MPN") "CM105X5R106M25AT"))
      (libsource (lib "eagle-import") (part "C0603US"))
    )
    (comp (ref "C86")
      (value "10uF")
      (footprint "eagle-import:SMD_1608M-0603US-C")
      (fields (field (name "MPN") "CM105X5R106M25AT"))
      (libsource (lib "eagle-import") (part "C0603US"))
    )
    (comp (ref "FB1")
      (value "BLM03PG330SN1D")
      (footprint "eagle-import:0201_FB")
      (fields (field (name "MANUFACTURER") "Murata"))
      (libsource (lib "eagle-import") (part "FERRITE_BEAD0201"))
    )
    (comp (ref "R1")
      (value "49.9-1%")
      (footprint "eagle-import:0201_RES")
      (fields (field (name "MPN") "ERJ-1GNF49R9C"))
      (libsource (lib "eagle-import") (part "passives_20904581_RESISTOR0201_RES"))
    )
    (comp (ref "R19")
      (value "100k")
      (footprint "eagle-import:0402_RES")
      (fields (field (name "MPN") "RT0402BRE07100KL"))
      (libsource (lib "eagle-import") (part "RESISTOR0402_RES"))
    )
    (comp (ref "RZ2")
      (value "0")
      (footprint "eagle-import:0603-RES")
      (fields (field (name "MPN") "RMCF0603ZT0R00"))
      (libsource (lib "eagle-import") (part "passives_20904581_RESISTOR0603_RES"))
    )
    (comp (ref "RZ3")
      (value "0")
      (footprint "eagle-import:0603-RES")
      (fields (field (name "MPN") "RMCF0603ZT0R00"))
      (libsource (lib "eagle-import") (part "passives_20904581_RESISTOR0603_RES"))
    )
    (comp (ref "S2")
      (value "SKY13373")
      (footprint "eagle-import:SKY13373")
      (fields (field (name "MANUFACTURER") "Skyworks") (field (name "MPN") "SKY13373-460LF"))
      (libsource (lib "eagle-import") (part "SKY13373"))
    )
    (comp (ref "S3")
      (value "SIP3241XSIP32414")
      (footprint "eagle-import:TDFN2X2X0P6-8")
      (fields (field (name "MANUFACTURER") "Vishay") (field (name "MPN") "SIP32414DNP-T1-GE4"))
      (libsource (lib "eagle-import") (part "SIP3241XSIP32414"))
    )
    (comp (ref "SJ2")
      (value "JUMPER-SMT_3_1-NC_TRACE_SILK")
      (footprint "eagle-import:SMT-JUMPER_3_1-NC_TRACE_SILK")
      (libsource (lib "eagle-import") (part "JUMPER-SMT_3_1-NC_TRACE_SILK"))
    )
    (comp (ref "SJ3")
      (value "JUMPER-SMT_3_1-NC_TRACE_SILK")
      (footprint "eagle-import:SMT-JUMPER_3_1-NC_TRACE_SILK")
      (libsource (lib "eagle-import") (part "JUMPER-SMT_3_1-NC_TRACE_SILK"))
    )
    (comp (ref "TP0")
      (value "TEST-POINT")
      (footprint "eagle-import:PAD.03X.03")
      (libsource (lib "eagle-import") (part "TEST-POINT"))
    )
    (comp (ref "TP1")
      (value "TEST-POINT")
      (footprint "eagle-import:PAD.03X.03")
      (libsource (lib "eagle-import") (part "TEST-POINT"))
    )
    (comp (ref "TP2")
      (value "TEST-POINT")
      (footprint "eagle-import:PAD.03X.03")
      (libsource (lib "eagle-import") (part "TEST-POINT"))
    )
    (comp (ref "TP3")
      (value "TEST-POINT")
      (footprint "eagle-import:PAD.03X.03")
      (libsource (lib "eagle-import") (part "TEST-POINT"))
    )
    (comp (ref "TP4")
      (value "TEST-POINT")
      (footprint "eagle-import:PAD.03X.03")
      (libsource (lib "eagle-import") (part "TEST-POINT"))
    )
    (comp (ref "TP5")
      (value "TEST-POINT")
      (footprint "eagle-import:PAD.03X.03")
      (libsource (lib "eagle-import") (part "TEST-POINT"))
    )
    (comp (ref "TP6")
      (value "TEST-POINT")
      (footprint "eagle-import:PAD.03X.03")
      (libsource (lib "eagle-import") (part "TEST-POINT"))
    )
    (comp (ref "TP7")
      (value "TEST-POINT")
      (footprint "eagle-import:PAD.03X.03")
      (libsource (lib "eagle-import") (part "TEST-POINT"))
    )
    (comp (ref "TP11")
      (value "TEST-POINT")
      (footprint "eagle-import:PAD.03X.03")
      (libsource (lib "eagle-import") (part "TEST-POINT"))
    )
    (comp (ref "TP12")
      (value "TEST-POINT")
      (footprint "eagle-import:PAD.03X.03")
      (libsource (lib "eagle-import") (part "TEST-POINT"))
    )
    (comp (ref "TP13")
      (value "TEST-POINT")
      (footprint "eagle-import:PAD.03X.03")
      (libsource (lib "eagle-import") (part "TEST-POINT"))
    )
    (comp (ref "TP14")
      (value "TEST-POINT")
      (footprint "eagle-import:PAD.03X.03")
      (libsource (lib "eagle-import") (part "TEST-POINT"))
    )
    (comp (ref "TP15")
      (value "TEST-POINT")
      (footprint "eagle-import:PAD.03X.03")
      (libsource (lib "eagle-import") (part "TEST-POINT"))
    )
    (comp (ref "U2")
      (value "DW3110")
      (footprint "eagle-import:WLCSP52")
      (fields (field (name "MANUFACTURER") "Qorvo"))
      (libsource (lib "eagle-import") (part "DW3110"))
    )
    (comp (ref "U7")
      (value "QM14068")
      (footprint "eagle-import:QM14068")
      (fields (field (name "MANUFACTURER") "Qorvo"))
      (libsource (lib "eagle-import") (part "QM14068"))
    )
    (comp (ref "VR3")
      (value "TPS7A0218PDQNR")
      (footprint "eagle-import:4-XDFN-EP")
      (libsource (lib "eagle-import") (part "TPS7A0218PDQNR"))
    )
    (comp (ref "X4")
      (value "TXC-8Y")
      (footprint "eagle-import:TXC-8Y")
      (fields
        (field (name "FREQ") "38.4 MHz")
        (field (name "MANUFACTURER") "TXC")
        (field (name "MPN") "8Y38472012")
      )
      (libsource (lib "eagle-import") (part "TXC-8Y"))
    )
    (comp (ref "C9")
      (value "22pF")
      (footprint "eagle-import:0201_CAP")
      (fields (field (name "MPN") "GRM0335C1H220FA01D"))
      (libsource (lib "eagle-import") (part "passives_20904581_CAPACITOR0201_CAP"))
    )
    (comp (ref "C10")
      (value "22pF")
      (footprint "eagle-import:0201_CAP")
      (fields (field (name "MPN") "GRM0335C1H220FA01D"))
      (libsource (lib "eagle-import") (part "passives_20904581_CAPACITOR0201_CAP"))
    )
    (comp (ref "C12")
      (value "470pF")
      (footprint "eagle-import:0402_CAP")
      (description "CAP CER 470PF 50V C0G/NP0 0402")
      (fields (field (name "MANUFACTURER") "Murata") (field (name "MPN") "GRM1555C1H471JA01J"))
      (libsource (lib "eagle-import") (part "passives_20904581_CAPACITOR0402_CAP"))
    )
    (comp (ref "C13")
      (value "470pF")
      (footprint "eagle-import:0402_CAP")
      (description "CAP CER 470PF 50V C0G/NP0 0402")
      (fields (field (name "MANUFACTURER") "Murata") (field (name "MPN") "GRM1555C1H471JA01J"))
      (libsource (lib "eagle-import") (part "passives_20904581_CAPACITOR0402_CAP"))
    )
    (comp (ref "C18")
      (value "10nF")
      (footprint "eagle-import:0402_CAP")
      (fields (field (name "MPN") "GRM155R71H103KA88J"))
      (libsource (lib "eagle-import") (part "passives_20904581_CAPACITOR0402_CAP"))
    )
    (comp (ref "C19")
      (value "10nF")
      (footprint "eagle-import:0402_CAP")
      (fields (field (name "MPN") "GRM155R71H103KA88J"))
      (libsource (lib "eagle-import") (part "passives_20904581_CAPACITOR0402_CAP"))
    )
    (comp (ref "C20")
      (value "22nF")
      (footprint "eagle-import:0402_CAP")
      (fields (field (name "MPN") "GRM155R71E223JA61D"))
      (libsource (lib "eagle-import") (part "passives_20904581_CAPACITOR0402_CAP"))
    )
    (comp (ref "C21")
      (value "22nF")
      (footprint "eagle-import:0402_CAP")
      (fields (field (name "MPN") "GRM155R71E223JA61D"))
      (libsource (lib "eagle-import") (part "passives_20904581_CAPACITOR0402_CAP"))
    )
    (comp (ref "C22")
      (value "22nF")
      (footprint "eagle-import:0402_CAP")
      (fields (field (name "MPN") "GRM155R71E223JA61D"))
      (libsource (lib "eagle-import") (part "passives_20904581_CAPACITOR0402_CAP"))
    )
    (comp (ref "C23")
      (value "22nF")
      (footprint "eagle-import:0402_CAP")
      (fields (field (name "MPN") "CC0402ZRY5V8BB223"))
      (libsource (lib "eagle-import") (part "passives_20904581_CAPACITOR0402_CAP"))
    )
    (comp (ref "C24")
      (value "22nF")
      (footprint "eagle-import:0402_CAP")
      (fields (field (name "MPN") "CC0402ZRY5V8BB223"))
      (libsource (lib "eagle-import") (part "passives_20904581_CAPACITOR0402_CAP"))
    )
    (comp (ref "C31")
      (value "0.1uF")
      (footprint "eagle-import:0402_CAP")
      (fields (field (name "MPN") "GRM155R71C104KA88J "))
      (libsource (lib "eagle-import") (part "CAPACITOR0402_CAP"))
    )
    (comp (ref "C32")
      (value "0.1uF")
      (footprint "eagle-import:0402_CAP")
      (fields (field (name "MPN") "GRM155R71C104KA88J "))
      (libsource (lib "eagle-import") (part "CAPACITOR0402_CAP"))
    )
    (comp (ref "C33")
      (value "0.1uF")
      (footprint "eagle-import:0402_CAP")
      (fields (field (name "MPN") "GRM155R71C104KA88J "))
      (libsource (lib "eagle-import") (part "CAPACITOR0402_CAP"))
    )
    (comp (ref "C34")
      (value "0.1uF")
      (footprint "eagle-import:0402_CAP")
      (fields (field (name "MPN") "GRM155R71C104KA88J "))
      (libsource (lib "eagle-import") (part "CAPACITOR0402_CAP"))
    )
    (comp (ref "C42")
      (value "0.47uF")
      (footprint "eagle-import:0402_CAP")
      (fields (field (name "MPN") "C1005X5R1E474K050BB"))
      (libsource (lib "eagle-import") (part "passives_20904581_CAPACITOR0402_CAP"))
    )
    (comp (ref "C43")
      (value "0.47uF")
      (footprint "eagle-import:0402_CAP")
      (fields (field (name "MPN") "C1005X5R1E474K050BB"))
      (libsource (lib "eagle-import") (part "passives_20904581_CAPACITOR0402_CAP"))
    )
    (comp (ref "C59")
      (value "1uF")
      (footprint "eagle-import:0201_CAP")
      (fields (field (name "MANUFACTURER") "Murata") (field (name "MPN") "GRM033R61A105ME44D"))
      (libsource (lib "eagle-import") (part "passives_20904581_CAPACITOR0201_CAP"))
    )
    (comp (ref "C60")
      (value "1uF")
      (footprint "eagle-import:0201_CAP")
      (fields (field (name "MANUFACTURER") "Murata") (field (name "MPN") "GRM033R61A105ME44D"))
      (libsource (lib "eagle-import") (part "passives_20904581_CAPACITOR0201_CAP"))
    )
    (comp (ref "C61")
      (value "1uF")
      (footprint "eagle-import:0201_CAP")
      (fields (field (name "MANUFACTURER") "Murata") (field (name "MPN") "GRM033R61A105ME44D"))
      (libsource (lib "eagle-import") (part "passives_20904581_CAPACITOR0201_CAP"))
    )
    (comp (ref "C76")
      (value "4.7uF")
      (footprint "eagle-import:0603_CAP")
      (fields (field (name "MPN") "C1608X7S1A475K080AC"))
      (libsource (lib "eagle-import") (part "passives_20904581_CAPACITOR0603_CAP"))
    )
    (comp (ref "C77")
      (value "4.7uF")
      (footprint "eagle-import:0603_CAP")
      (fields (field (name "MPN") "C1608X7S1A475K080AC"))
      (libsource (lib "eagle-import") (part "passives_20904581_CAPACITOR0603_CAP"))
    )
    (comp (ref "C78")
      (value "4.7uF")
      (footprint "eagle-import:0603_CAP")
      (fields (field (name "MPN") "C1608X7S1A475K080AC"))
      (libsource (lib "eagle-import") (part "passives_20904581_CAPACITOR0603_CAP"))
    )
    (comp (ref "C79")
      (value "4.7uF")
      (footprint "eagle-import:0603_CAP")
      (fields (field (name "MPN") "C1608X7S1A475K080AC"))
      (libsource (lib "eagle-import") (part "passives_20904581_CAPACITOR0603_CAP"))
    )
    (comp (ref "C82")
      (value "10uF")
      (footprint "eagle-import:0603_CAP")
      (fields (field (name "MPN") "CM105X5R106M25AT"))
      (libsource (lib "eagle-import") (part "passives_20904581_CAPACITOR0603_CAP"))
    )
    (comp (ref "C83")
      (value "10uF")
      (footprint "eagle-import:0603_CAP")
      (fields (field (name "MPN") "CM105X5R106M25AT"))
      (libsource (lib "eagle-import") (part "passives_20904581_CAPACITOR0603_CAP"))
    )
    (comp (ref "C84")
      (value "10uF")
      (footprint "eagle-import:0603_CAP")
      (fields (field (name "MPN") "CM105X5R106M25AT"))
      (libsource (lib "eagle-import") (part "passives_20904581_CAPACITOR0603_CAP"))
    )
    (comp (ref "J3")
      (value "PINHD-1X2")
      (footprint "eagle-import:1X02")
      (libsource (lib "eagle-import") (part "PINHD-1X2"))
    )
    (comp (ref "J4")
      (value "MOLEX-PICO-SPOX-3SIDE")
      (footprint "eagle-import:MOLEX-PICO-SPOX-3_SIDE")
      (libsource (lib "eagle-import") (part "MOLEX-PICO-SPOX-3SIDE"))
    )
    (comp (ref "J5")
      (value "PINHD-1X1")
      (footprint "eagle-import:1X01")
      (libsource (lib "eagle-import") (part "PINHD-1X1"))
    )
    (comp (ref "J6")
      (value "PINHD-1X1")
      (footprint "eagle-import:1X01")
      (libsource (lib "eagle-import") (part "PINHD-1X1"))
    )
    (comp (ref "J7")
      (value "USB4110-GF-A")
      (footprint "eagle-import:GCT_USB4110-GF-A")
      (fields (field (name "MF") "GCT"))
      (libsource (lib "eagle-import") (part "USB4110-GF-A"))
    )
    (comp (ref "L1")
      (value "10uH")
      (footprint "eagle-import:NRX3015")
      (fields (field (name "MANUFACTURER") "TAIYO YUDEN") (field (name "MPN") "NR3015T100M"))
      (libsource (lib "eagle-import") (part "INDUCTORNRX3015"))
    )
    (comp (ref "L2")
      (value "10uH")
      (footprint "eagle-import:NRX3015")
      (fields (field (name "MANUFACTURER") "TAIYO YUDEN") (field (name "MPN") "NR3015T100M"))
      (libsource (lib "eagle-import") (part "INDUCTORNRX3015"))
    )
    (comp (ref "L4")
      (value "WURTH_COIL_760308103204")
      (footprint "eagle-import:WURTH_COIL_760308103204")
      (fields (field (name "MANUFACTURER") "Würth Elektronik") (field (name "MPN") "760308103204"))
      (libsource (lib "eagle-import") (part "WURTH_COIL_760308103204"))
    )
    (comp (ref "Q1")
      (value "CSD75207W15")
      (footprint "eagle-import:DSBGA")
      (fields (field (name "MANUFACTURER") "TEXAS INSTRUMENTS"))
      (libsource (lib "eagle-import") (part "CSD75207W15"))
    )
    (comp (ref "R6")
      (value "97.6")
      (footprint "eagle-import:0402_RES")
      (fields (field (name "MPN") "RMCF0402FT97R6"))
      (libsource (lib "eagle-import") (part "passives_20904581_RESISTOR0402_RES"))
    )
    (comp (ref "R7")
      (value "97.6")
      (footprint "eagle-import:0402_RES")
      (fields (field (name "MPN") "RMCF0402FT97R6"))
      (libsource (lib "eagle-import") (part "passives_20904581_RESISTOR0402_RES"))
    )
    (comp (ref "R8")
      (value "162")
      (footprint "eagle-import:0402_RES")
      (fields (field (name "MPN") "RMCF0402FT162R"))
      (libsource (lib "eagle-import") (part "passives_20904581_RESISTOR0402_RES"))
    )
    (comp (ref "R9")
      (value "162")
      (footprint "eagle-import:0402_RES")
      (fields (field (name "MPN") "RMCF0402FT162R"))
      (libsource (lib "eagle-import") (part "passives_20904581_RESISTOR0402_RES"))
    )
    (comp (ref "R10")
      (value "2.2k")
      (footprint "eagle-import:0402_RES")
      (fields (field (name "MPN") "RC0402FR-072K2L") (field (name "TOL") "1%"))
      (libsource (lib "eagle-import") (part "RESISTOR0402_RES"))
    )
    (comp (ref "R11")
      (value "2.2k")
      (footprint "eagle-import:0402_RES")
      (fields (field (name "MPN") "RC0402FR-072K2L"))
      (libsource (lib "eagle-import") (part "passives_20904581_RESISTOR0402_RES"))
    )
    (comp (ref "R12")
      (value "5.1k")
      (footprint "eagle-import:0402_RES")
      (fields (field (name "MPN") "RMCF0402FT5K10"))
      (libsource (lib "eagle-import") (part "passives_20904581_RESISTOR0402_RES"))
    )
    (comp (ref "R13")
      (value "5.1k")
      (footprint "eagle-import:0402_RES")
      (fields (field (name "MPN") "RMCF0402FT5K10"))
      (libsource (lib "eagle-import") (part "passives_20904581_RESISTOR0402_RES"))
    )
    (comp (ref "R17")
      (value "10k")
      (footprint "eagle-import:0402_RES")
      (fields (field (name "MPN") "RC0402JR-0710KL"))
      (libsource (lib "eagle-import") (part "RESISTOR0402_RES"))
    )
    (comp (ref "R18")
      (value "10k")
      (footprint "eagle-import:0402_RES")
      (fields (field (name "MPN") "RC0402JR-0710KL"))
      (libsource (lib "eagle-import") (part "RESISTOR0402_RES"))
    )
    (comp (ref "R21")
      (value "261k")
      (footprint "eagle-import:0201_RES")
      (fields (field (name "MPN") "ERJ-1GNF2613C"))
      (libsource (lib "eagle-import") (part "passives_20904581_RESISTOR0201_RES"))
    )
    (comp (ref "R22")
      (value "402k")
      (footprint "eagle-import:0201_RES")
      (fields (field (name "MPN") "ERJ-1GNF4023C"))
      (libsource (lib "eagle-import") (part "passives_20904581_RESISTOR0201_RES"))
    )
    (comp (ref "R24")
      (value "845k")
      (footprint "eagle-import:0201_RES")
      (fields (field (name "MPN") "ERJ-1GNF8453C"))
      (libsource (lib "eagle-import") (part "passives_20904581_RESISTOR0201_RES"))
    )
    (comp (ref "R25")
      (value "845k")
      (footprint "eagle-import:0201_RES")
      (fields (field (name "MPN") "ERJ-1GNF8453C"))
      (libsource (lib "eagle-import") (part "passives_20904581_RESISTOR0201_RES"))
    )
    (comp (ref "R27")
      (value "1.87M")
      (footprint "eagle-import:0402_RES")
      (fields (field (name "MPN") "RMCF0402FT1M87") (field (name "TOLERANCE") "1%"))
      (libsource (lib "eagle-import") (part "RESISTOR0402_RES"))
    )
    (comp (ref "R28")
      (value "5.1M")
      (footprint "eagle-import:0402_RES")
      (fields (field (name "MPN") "RMCF0402FT5M10") (field (name "TOLERANCE") "1%"))
      (libsource (lib "eagle-import") (part "RESISTOR0402_RES"))
    )
    (comp (ref "R29")
      (value "5.1M")
      (footprint "eagle-import:0402_RES")
      (fields (field (name "MPN") "RMCF0402FT5M10"))
      (libsource (lib "eagle-import") (part "RESISTOR0402_RES"))
    )
    (comp (ref "R30")
      (value "5.1M")
      (footprint "eagle-import:0402_RES")
      (fields (field (name "MPN") "RMCF0402FT5M10"))
      (libsource (lib "eagle-import") (part "RESISTOR0402_RES"))
    )
    (comp (ref "RT1")
      (value "10k@25C")
      (footprint "eagle-import:0402_RES")
      (fields (field (name "MPN") "NCU15XH103F60RC"))
      (libsource (lib "eagle-import") (part "THERMISTOR0402"))
    )
    (comp (ref "RX1")
      (value "DNP")
      (footprint "eagle-import:0402_RES")
      (libsource (lib "eagle-import") (part "RESISTOR0402_RES"))
    )
    (comp (ref "RX2")
      (value "DNP")
      (footprint "eagle-import:0402_RES")
      (libsource (lib "eagle-import") (part "passives_20904581_RESISTOR0402_RES"))
    )
    (comp (ref "S1")
      (value "450404015514")
      (footprint "eagle-import:450404015514")
      (libsource (lib "eagle-import") (part "450404015514"))
    )
    (comp (ref "SJ1")
      (value "JUMPER-SMT_3_1-NC_TRACE_SILK")
      (footprint "eagle-import:SMT-JUMPER_3_1-NC_TRACE_SILK")
      (libsource (lib "eagle-import") (part "JUMPER-SMT_3_1-NC_TRACE_SILK"))
    )
    (comp (ref "U3")
      (value "BQ24040")
      (footprint "eagle-import:DSQ0010A")
      (fields (field (name "MPN") "BQ24040DSQR"))
      (libsource (lib "eagle-import") (part "BQ24040"))
    )
    (comp (ref "U4")
      (value "BQ51013B")
      (footprint "eagle-import:RHL0020A")
      (fields (field (name "MPN") "BQ51013BRHLR"))
      (libsource (lib "eagle-import") (part "BQ51013B"))
    )
    (comp (ref "VR1")
      (value "RT8020RT8020GQW")
      (footprint "eagle-import:SON45P300X300X80-13T160X250N")
      (fields (field (name "MANUFACTURER") "RichTek") (field (name "MPN") "RT8020GQW"))
      (libsource (lib "eagle-import") (part "RT8020RT8020GQW"))
    )
    (comp (ref "C47")
      (value "1uF")
      (footprint "eagle-import:0201_CAP")
      (fields (field (name "MANUFACTURER") "Murata") (field (name "MPN") "GRM033R61A105ME44D"))
      (libsource (lib "eagle-import") (part "passives_20904581_CAPACITOR0201_CAP"))
    )
    (comp (ref "C48")
      (value "1uF")
      (footprint "eagle-import:0201_CAP")
      (fields (field (name "MANUFACTURER") "Murata") (field (name "MPN") "GRM033R61A105ME44D"))
      (libsource (lib "eagle-import") (part "passives_20904581_CAPACITOR0201_CAP"))
    )
    (comp (ref "C50")
      (value "1uF")
      (footprint "eagle-import:0201_CAP")
      (fields (field (name "MANUFACTURER") "Murata") (field (name "MPN") "GRM033R61A105ME44D"))
      (libsource (lib "eagle-import") (part "passives_20904581_CAPACITOR0201_CAP"))
    )
    (comp (ref "C51")
      (value "1uF")
      (footprint "eagle-import:0201_CAP")
      (fields (field (name "MANUFACTURER") "Murata") (field (name "MPN") "GRM033R61A105ME44D"))
      (libsource (lib "eagle-import") (part "passives_20904581_CAPACITOR0201_CAP"))
    )
    (comp (ref "C52")
      (value "1uF")
      (footprint "eagle-import:0201_CAP")
      (fields (field (name "MANUFACTURER") "Murata") (field (name "MPN") "GRM033R61A105ME44D"))
      (libsource (lib "eagle-import") (part "passives_20904581_CAPACITOR0201_CAP"))
    )
    (comp (ref "C57")
      (value "1uF")
      (footprint "eagle-import:0201_CAP")
      (fields (field (name "MANUFACTURER") "Murata") (field (name "MPN") "GRM033R61A105ME44D"))
      (libsource (lib "eagle-import") (part "passives_20904581_CAPACITOR0201_CAP"))
    )
    (comp (ref "D1")
      (value "BICOLOR-SMD")
      (footprint "eagle-import:LED-0606")
      (fields (field (name "MPN") "MCL0606FRD1GR1T"))
      (libsource (lib "eagle-import") (part "BICOLOR-SMD"))
    )
    (comp (ref "D2")
      (value "BICOLOR-SMD")
      (footprint "eagle-import:LED-0606")
      (fields (field (name "MPN") "MCL0606FYW1RD1T"))
      (libsource (lib "eagle-import") (part "BICOLOR-SMD"))
    )
    (comp (ref "D5")
      (value "DIODE_TVS_ARRAY-2")
      (footprint "eagle-import:SOT143B")
      (fields (field (name "MPN") "PRTR5V0U2X,215"))
      (libsource (lib "eagle-import") (part "DIODE_TVS_ARRAY-2"))
    )
    (comp (ref "J1")
      (value "TC2030-JLINK-NL-2SIDE")
      (footprint "eagle-import:TC2030-IDC-NL-2SIDE")
      (libsource (lib "eagle-import") (part "TC2030-JLINK-NL-2SIDE"))
    )
    (comp (ref "R2")
      (value "5.1")
      (footprint "eagle-import:0402_RES")
      (fields (field (name "MPN") "RC0402JR-075R1L"))
      (libsource (lib "eagle-import") (part "RESISTOR0402_RES"))
    )
    (comp (ref "R3")
      (value "5.1")
      (footprint "eagle-import:0402_RES")
      (fields (field (name "MPN") "RC0402JR-075R1L"))
      (libsource (lib "eagle-import") (part "RESISTOR0402_RES"))
    )
    (comp (ref "R4")
      (value "15")
      (footprint "eagle-import:0402_RES")
      (fields (field (name "MPN") "RC0402JR-0715RL"))
      (libsource (lib "eagle-import") (part "RESISTOR0402_RES"))
    )
    (comp (ref "R5")
      (value "15")
      (footprint "eagle-import:0402_RES")
      (fields (field (name "MPN") "RC0402JR-0715RL"))
      (libsource (lib "eagle-import") (part "RESISTOR0402_RES"))
    )
    (comp (ref "R23")
      (value "402k")
      (footprint "eagle-import:0201_RES")
      (fields (field (name "MPN") "ERJ-1GNF4023C"))
      (libsource (lib "eagle-import") (part "passives_20904581_RESISTOR0201_RES"))
    )
    (comp (ref "R26")
      (value "845k")
      (footprint "eagle-import:0201_RES")
      (fields (field (name "MPN") "ERJ-1GNF8453C"))
      (libsource (lib "eagle-import") (part "passives_20904581_RESISTOR0201_RES"))
    )
    (comp (ref "SJ7")
      (value "JUMPER-SMT_2_NC_TRACE_SILK")
      (footprint "eagle-import:SMT-JUMPER_2_NC_TRACE_SILK")
      (libsource (lib "eagle-import") (part "JUMPER-SMT_2_NC_TRACE_SILK"))
    )
    (comp (ref "SJ9")
      (value "JUMPER-SMT_2_NC_TRACE_SILK")
      (footprint "eagle-import:SMT-JUMPER_2_NC_TRACE_SILK")
      (libsource (lib "eagle-import") (part "JUMPER-SMT_2_NC_TRACE_SILK"))
    )
    (comp (ref "SJ10")
      (value "JUMPER-SMT_2_NC_TRACE_SILK")
      (footprint "eagle-import:SMT-JUMPER_2_NC_TRACE_SILK")
      (libsource (lib "eagle-import") (part "JUMPER-SMT_2_NC_TRACE_SILK"))
    )
    (comp (ref "VR2")
      (value "TPS7A0218PDQNR")
      (footprint "eagle-import:4-XDFN-EP")
      (libsource (lib "eagle-import") (part "TPS7A0218PDQNR"))
    )
    (comp (ref "VR4")
      (value "TPS7A0233PDQNR")
      (footprint "eagle-import:4-XDFN-EP")
      (libsource (lib "eagle-import") (part "TPS7A0233PDQNR"))
    )
    (comp (ref "VR5")
      (value "TPS7A0309PDBVR")
      (footprint "eagle-import:DBV0005A--SOT23-5-VARIANT")
      (libsource (lib "eagle-import") (part "TPS7A0309PDBVR"))
    )
  )
  (nets
    (net (code "1") (name "+1V8") (class "Default")
      (node (ref "C10") (pin "P$2") (pinfunction "2_P$2") (pintype "bidirectional"))
      (node (ref "C30") (pin "1") (pinfunction "1_1") (pintype "bidirectional"))
      (node (ref "C35") (pin "1") (pinfunction "1_1") (pintype "bidirectional"))
      (node (ref "C39") (pin "1") (pinfunction "1_1") (pintype "bidirectional"))
      (node (ref "C53") (pin "P$1") (pinfunction "1_P$1") (pintype "bidirectional"))
      (node (ref "C54") (pin "P$1") (pinfunction "1_P$1") (pintype "bidirectional"))
      (node (ref "C55") (pin "P$1") (pinfunction "1_P$1") (pintype "bidirectional"))
      (node (ref "C56") (pin "P$1") (pinfunction "1_P$1") (pintype "bidirectional"))
      (node (ref "C71") (pin "P$2") (pinfunction "2_P$2") (pintype "bidirectional"))
      (node (ref "C74") (pin "P$1") (pinfunction "1_P$1") (pintype "bidirectional"))
      (node (ref "C77") (pin "1") (pinfunction "1_1") (pintype "bidirectional"))
      (node (ref "C81") (pin "2") (pinfunction "2_2") (pintype "bidirectional"))
      (node (ref "D1") (pin "A1") (pinfunction "A1_A1") (pintype "bidirectional"))
      (node (ref "D1") (pin "A2") (pinfunction "A2_A2") (pintype "bidirectional"))
      (node (ref "D2") (pin "A1") (pinfunction "A1_A1") (pintype "bidirectional"))
      (node (ref "D2") (pin "A2") (pinfunction "A2_A2") (pintype "bidirectional"))
      (node (ref "J1") (pin "1") (pinfunction "VTREF_1") (pintype "bidirectional"))
      (node (ref "J1") (pin "B1") (pinfunction "VTREF_B1") (pintype "bidirectional"))
      (node (ref "J6") (pin "1") (pinfunction "1_1") (pintype "passive"))
      (node (ref "L2") (pin "P$1") (pinfunction "1_P$1") (pintype "bidirectional"))
      (node (ref "R14") (pin "2") (pinfunction "2_2") (pintype "passive"))
      (node (ref "R15") (pin "2") (pinfunction "2_2") (pintype "passive"))
      (node (ref "R16") (pin "2") (pinfunction "2_2") (pintype "passive"))
      (node (ref "R25") (pin "1") (pinfunction "1_1") (pintype "passive"))
      (node (ref "RX3") (pin "2") (pinfunction "2_2") (pintype "passive"))
      (node (ref "RX4") (pin "1") (pinfunction "1_1") (pintype "passive"))
      (node (ref "RX5") (pin "1") (pinfunction "1_1") (pintype "passive"))
      (node (ref "S3") (pin "4") (pinfunction "IN_4") (pintype "bidirectional"))
      (node (ref "SJ2") (pin "1") (pinfunction "1_1") (pintype "passive"))
      (node (ref "SJ4") (pin "3") (pinfunction "3_3") (pintype "passive"))
      (node (ref "SJ8") (pin "1") (pinfunction "1_1") (pintype "passive"))
      (node (ref "TP9") (pin "P$1") (pinfunction "TESTPOINT_P$1") (pintype "bidirectional"))
      (node (ref "U1") (pin "B1") (pinfunction "VDDP-IO_PAD_SUP_B1") (pintype "bidirectional"))
      (node (ref "U1") (pin "C4") (pinfunction "VDDA-ANALOG_SUP_C4") (pintype "bidirectional"))
      (node (ref "U1") (pin "E11") (pinfunction "VDDAUDD_E11") (pintype "bidirectional"))
      (node (ref "U1") (pin "M10") (pinfunction "VDDH-HV_SUP_M10") (pintype "bidirectional"))
      (node (ref "U1") (pin "M9") (pinfunction "VDDH2-HV_SUP_M9") (pintype "bidirectional"))
      (node (ref "U2") (pin "B13") (pinfunction "VDD1_B13") (pintype "bidirectional"))
      (node (ref "U6") (pin "28") (pinfunction "VDDIO_28") (pintype "input"))
      (node (ref "U8") (pin "8") (pinfunction "VCC_8") (pintype "bidirectional"))
    )
    (net (code "2") (name "+2V5") (class "Default")
      (node (ref "C36") (pin "1") (pinfunction "1_1") (pintype "bidirectional"))
      (node (ref "C38") (pin "1") (pinfunction "1_1") (pintype "bidirectional"))
      (node (ref "C44") (pin "P$1") (pinfunction "1_P$1") (pintype "bidirectional"))
      (node (ref "C47") (pin "P$1") (pinfunction "1_P$1") (pintype "bidirectional"))
      (node (ref "C58") (pin "P$1") (pinfunction "1_P$1") (pintype "bidirectional"))
      (node (ref "C78") (pin "2") (pinfunction "2_2") (pintype "bidirectional"))
      (node (ref "C80") (pin "1") (pinfunction "1_1") (pintype "bidirectional"))
      (node (ref "C9") (pin "P$1") (pinfunction "1_P$1") (pintype "bidirectional"))
      (node (ref "D4") (pin "CATHODE") (pinfunction "CATHODE_CATHODE") (pintype "bidirectional"))
      (node (ref "J5") (pin "1") (pinfunction "1_1") (pintype "passive"))
      (node (ref "L1") (pin "P$2") (pinfunction "2_P$2") (pintype "bidirectional"))
      (node (ref "LS1") (pin "+") (pinfunction "P_+") (pintype "passive"))
      (node (ref "R24") (pin "2") (pinfunction "2_2") (pintype "passive"))
      (node (ref "S2") (pin "6") (pinfunction "VDD_6") (pintype "power_in"))
      (node (ref "S3") (pin "1") (pinfunction "IN_1") (pintype "bidirectional"))
      (node (ref "U6") (pin "3") (pinfunction "VDD_3") (pintype "input"))
      (node (ref "VR2") (pin "3") (pinfunction "EN_3") (pintype "input"))
      (node (ref "VR2") (pin "4") (pinfunction "IN_4") (pintype "bidirectional"))
      (node (ref "VR3") (pin "4") (pinfunction "IN_4") (pintype "bidirectional"))
    )
    (net (code "3") (name "9DOF_H_SDA{slash}H_MISO{slash}TX") (class "Default")
      (node (ref "RX4") (pin "2") (pinfunction "2_2") (pintype "passive"))
      (node (ref "SJ5") (pin "1") (pinfunction "1_1") (pintype "passive"))
      (node (ref "SJ6") (pin "2") (pinfunction "2_2") (pintype "passive"))
      (node (ref "U6") (pin "20") (pinfunction "H_SDA/H_MISO/TX_20") (pintype "bidirectional"))
    )
    (net (code "4") (name "9DOF_SA0{slash}H_MOSI") (class "Default")
      (node (ref "SJ5") (pin "2") (pinfunction "2_2") (pintype "passive"))
      (node (ref "SJ6") (pin "1") (pinfunction "1_1") (pintype "passive"))
      (node (ref "U6") (pin "17") (pinfunction "SA0/H_MOSI_17") (pintype "input"))
    )
    (net (code "5") (name "AGND") (class "Default")
      (node (ref "C1") (pin "2") (pinfunction "2_2") (pintype "passive"))
      (node (ref "C46") (pin "P$2") (pinfunction "2_P$2") (pintype "bidirectional"))
      (node (ref "U1") (pin "M1") (pinfunction "RFIOM_M1") (pintype "bidirectional"))
      (node (ref "U1") (pin "M3") (pinfunction "RFSUB-RF_SUBSTRATE_GND_M3") (pintype "bidirectional"))
    )
    (net (code "6") (name "AP4_GP06{slash}TT_FLASH_~{HOLD_IO3}") (class "Default")
      (node (ref "U1") (pin "J5") (pinfunction "GPIO6_J5") (pintype "bidirectional"))
      (node (ref "U8") (pin "7") (pinfunction "~{HOLD}/SIO3_7") (pintype "bidirectional"))
    )
    (net (code "7") (name "AP4_GP08{slash}TT_9DOF_H_SCL{slash}SCK{slash}RX") (class "Default")
      (node (ref "RX5") (pin "2") (pinfunction "2_2") (pintype "passive"))
      (node (ref "U1") (pin "H2") (pinfunction "GPIO31_H2") (pintype "bidirectional"))
      (node (ref "U6") (pin "19") (pinfunction "H_SCL/SCK/RX_19") (pintype "bidirectional"))
    )
    (net (code "8") (name "AP4_GP09{slash}TT_9DOF_H_MOSI") (class "Default")
      (node (ref "SJ5") (pin "3") (pinfunction "3_3") (pintype "passive"))
      (node (ref "U1") (pin "G2") (pinfunction "GPIO32_G2") (pintype "bidirectional"))
    )
    (net (code "9") (name "AP4_GP10{slash}TT_9DOF_H_MISO") (class "Default")
      (node (ref "SJ6") (pin "3") (pinfunction "3_3") (pintype "passive"))
      (node (ref "U1") (pin "G3") (pinfunction "GPIO33_G3") (pintype "bidirectional"))
    )
    (net (code "10") (name "AP4_GP13{slash}TT_9DOF_~{BOOT}") (class "Default")
      (node (ref "R14") (pin "1") (pinfunction "1_1") (pintype "passive"))
      (node (ref "U1") (pin "D5") (pinfunction "GPIO13_D5") (pintype "bidirectional"))
      (node (ref "U6") (pin "4") (pinfunction "~{BOOT}_4") (pintype "input"))
    )
    (net (code "11") (name "AP4_GP14{slash}TT_~{DW_SPI_CS}") (class "Default")
      (node (ref "TP12") (pin "P$1") (pinfunction "TESTPOINT_P$1") (pintype "bidirectional"))
      (node (ref "U1") (pin "D6") (pinfunction "GPIO14_D6") (pintype "bidirectional"))
      (node (ref "U2") (pin "B5") (pinfunction "~{SPICS}_B5") (pintype "bidirectional"))
    )
    (net (code "12") (name "AP4_GP17{slash}TT_9DOF_H_~{INT}") (class "Default")
      (node (ref "U1") (pin "D4") (pinfunction "GPIO17_D4") (pintype "bidirectional"))
      (node (ref "U6") (pin "14") (pinfunction "H_INTN_14") (pintype "output"))
    )
    (net (code "13") (name "AP4_GP18{slash}TT_BATIN") (class "Default")
      (node (ref "C31") (pin "1") (pinfunction "1_1") (pintype "bidirectional"))
      (node (ref "R27") (pin "2") (pinfunction "2_2") (pintype "passive"))
      (node (ref "R28") (pin "1") (pinfunction "1_1") (pintype "passive"))
      (node (ref "U1") (pin "D3") (pinfunction "GPIO18_D3") (pintype "bidirectional"))
    )
    (net (code "14") (name "AP4_GP24{slash}TT_RFSW_V1") (class "Default")
      (node (ref "S2") (pin "4") (pinfunction "V1_4") (pintype "input"))
      (node (ref "U1") (pin "E2") (pinfunction "GPIO24_E2") (pintype "bidirectional"))
    )
    (net (code "15") (name "AP4_GP25{slash}TT_RFSW_V2") (class "Default")
      (node (ref "S2") (pin "5") (pinfunction "V2_5") (pintype "input"))
      (node (ref "U1") (pin "K5") (pinfunction "GPIO25_K5") (pintype "bidirectional"))
    )
    (net (code "16") (name "AP4_GP26{slash}TT_DW_WAKEUP") (class "Default")
      (node (ref "U1") (pin "L5") (pinfunction "GPIO26_L5") (pintype "bidirectional"))
      (node (ref "U2") (pin "B9") (pinfunction "WAKEUP_B9") (pintype "bidirectional"))
    )
    (net (code "17") (name "AP4_GP27{slash}TT_DW_IRQ") (class "Default")
      (node (ref "R19") (pin "2") (pinfunction "2_2") (pintype "passive"))
      (node (ref "U1") (pin "M5") (pinfunction "GPIO27_M5") (pintype "bidirectional"))
      (node (ref "U2") (pin "B1") (pinfunction "IRQ/GPIO8_B1") (pintype "bidirectional"))
    )
    (net (code "18") (name "AP4_GP30{slash}TT_FLASH_~{WP}") (class "Default")
      (node (ref "U1") (pin "G4") (pinfunction "GPIO30_G4") (pintype "bidirectional"))
      (node (ref "U8") (pin "3") (pinfunction "~{WP}/SIO2_3") (pintype "bidirectional"))
    )
    (net (code "19") (name "AP4_GP31{slash}TT_DW_SPI_CLK") (class "Default")
      (node (ref "TP11") (pin "P$1") (pinfunction "TESTPOINT_P$1") (pintype "bidirectional"))
      (node (ref "U1") (pin "E8") (pinfunction "GPIO8_E8") (pintype "bidirectional"))
      (node (ref "U2") (pin "A8") (pinfunction "SPICLK_A8") (pintype "bidirectional"))
    )
    (net (code "20") (name "AP4_GP32{slash}TT_DW_SPI_IO0") (class "Default")
      (node (ref "TP13") (pin "P$1") (pinfunction "TESTPOINT_P$1") (pintype "bidirectional"))
      (node (ref "U1") (pin "E7") (pinfunction "GPIO9_E7") (pintype "bidirectional"))
      (node (ref "U2") (pin "B7") (pinfunction "SPICDI(MOSI)_B7") (pintype "bidirectional"))
    )
    (net (code "21") (name "AP4_GP33{slash}TT_DW_SPI_IO1") (class "Default")
      (node (ref "TP14") (pin "P$1") (pinfunction "TESTPOINT_P$1") (pintype "bidirectional"))
      (node (ref "U1") (pin "E6") (pinfunction "GPIO10_E6") (pintype "bidirectional"))
      (node (ref "U2") (pin "A6") (pinfunction "SPICDO(MISO)_A6") (pintype "bidirectional"))
    )
    (net (code "22") (name "AP4_GP47{slash}TT_FLASH_SCK") (class "Default")
      (node (ref "U1") (pin "F1") (pinfunction "GPIO47_F1") (pintype "bidirectional"))
      (node (ref "U8") (pin "6") (pinfunction "SCLK_6") (pintype "input"))
    )
    (net (code "23") (name "AP4_GP48{slash}TT_FLASH_PDI_IO0") (class "Default")
      (node (ref "U1") (pin "E1") (pinfunction "GPIO48_E1") (pintype "bidirectional"))
      (node (ref "U8") (pin "5") (pinfunction "SI/SIO0_5") (pintype "bidirectional"))
    )
    (net (code "24") (name "AP4_GP49{slash}TT_FLASH_PDO_IO1") (class "Default")
      (node (ref "U1") (pin "D1") (pinfunction "GPIO49_D1") (pintype "bidirectional"))
      (node (ref "U8") (pin "2") (pinfunction "SO/SIO1_2") (pintype "bidirectional"))
    )
    (net (code "25") (name "AP4_GP50{slash}TT_~{DW_RESET}") (class "Default")
      (node (ref "TP15") (pin "P$1") (pinfunction "TESTPOINT_P$1") (pintype "bidirectional"))
      (node (ref "U1") (pin "A9") (pinfunction "GPIO50_A9") (pintype "bidirectional"))
      (node (ref "U2") (pin "A10") (pinfunction "~{RST}_A10") (pintype "bidirectional"))
    )
    (net (code "26") (name "AP4_GP51{slash}LED1_GREEN") (class "Default")
      (node (ref "R2") (pin "2") (pinfunction "2_2") (pintype "passive"))
      (node (ref "U1") (pin "B9") (pinfunction "GPIO51_B9") (pintype "bidirectional"))
    )
    (net (code "27") (name "AP4_GP53{slash}LED1_RED") (class "Default")
      (node (ref "R5") (pin "2") (pinfunction "2_2") (pintype "passive"))
      (node (ref "U1") (pin "C9") (pinfunction "GPIO53_C9") (pintype "bidirectional"))
    )
    (net (code "28") (name "AP4_GP55{slash}TT_BUZZER_GATE") (class "Default")
      (node (ref "Q2") (pin "G") (pinfunction "G_G") (pintype "passive"))
      (node (ref "R20") (pin "1") (pinfunction "1_1") (pintype "passive"))
      (node (ref "U1") (pin "D9") (pinfunction "GPIO55_D9") (pintype "bidirectional"))
    )
    (net (code "29") (name "AP4_GP58{slash}TT_~{CHG}") (class "Default")
      (node (ref "U1") (pin "J7") (pinfunction "GPIO58_J7") (pintype "bidirectional"))
      (node (ref "U3") (pin "8") (pinfunction "~{CHG}_8") (pintype "bidirectional"))
      (node (ref "U4") (pin "7") (pinfunction "~{CHG}_7") (pintype "bidirectional"))
    )
    (net (code "30") (name "AP4_GP60{slash}TT_~{PG}") (class "Default")
      (node (ref "U1") (pin "K8") (pinfunction "GPIO60_K8") (pintype "bidirectional"))
      (node (ref "U3") (pin "5") (pinfunction "~{PG}_5") (pintype "bidirectional"))
    )
    (net (code "31") (name "AP4_GP63{slash}TT_9DOF_PS0{slash}WAKE") (class "Default")
      (node (ref "U1") (pin "M6") (pinfunction "GPIO63_M6") (pintype "bidirectional"))
      (node (ref "U6") (pin "6") (pinfunction "PS0/WAKE_6") (pintype "input"))
    )
    (net (code "32") (name "AP4_GP65{slash}TT_9DOF_~{RESET}") (class "Default")
      (node (ref "U1") (pin "A7") (pinfunction "GPIO65_A7") (pintype "bidirectional"))
      (node (ref "U6") (pin "11") (pinfunction "~{RESET}_11") (pintype "input"))
    )
    (net (code "33") (name "AP4_GP66{slash}TT_QI_TS_CTRL") (class "Default")
      (node (ref "C34") (pin "1") (pinfunction "1_1") (pintype "bidirectional"))
      (node (ref "RT1") (pin "2") (pinfunction "2_2") (pintype "passive"))
      (node (ref "U1") (pin "A8") (pinfunction "GPIO66_A8") (pintype "bidirectional"))
      (node (ref "U4") (pin "13") (pinfunction "TS/CTRL_13") (pintype "bidirectional"))
    )
    (net (code "34") (name "AP4_GP69{slash}TT_FLASH_~{CS}") (class "Default")
      (node (ref "RX3") (pin "1") (pinfunction "1_1") (pintype "passive"))
      (node (ref "U1") (pin "B8") (pinfunction "GPIO69_B8") (pintype "bidirectional"))
      (node (ref "U8") (pin "1") (pinfunction "~{CS}_1") (pintype "input"))
    )
    (net (code "35") (name "AP4_GP72{slash}TT_9DOF_H_~{CS}") (class "Default")
      (node (ref "U1") (pin "C8") (pinfunction "GPIO72_C8") (pintype "bidirectional"))
      (node (ref "U6") (pin "18") (pinfunction "H_~{CS}_18") (pintype "input"))
    )
    (net (code "36") (name "AP4_GP78{slash}VR-EN_USB0P9") (class "Default")
      (node (ref "U1") (pin "L11") (pinfunction "GPIO78_L11") (pintype "bidirectional"))
      (node (ref "VR5") (pin "3") (pinfunction "EN_3") (pintype "input"))
    )
    (net (code "37") (name "AP4_GP79{slash}LED2_RED") (class "Default")
      (node (ref "R4") (pin "2") (pinfunction "2_2") (pintype "passive"))
      (node (ref "U1") (pin "M11") (pinfunction "GPIO79_M11") (pintype "bidirectional"))
    )
    (net (code "38") (name "AP4_GP80{slash}USB_CABLE_DETECT") (class "Default")
      (node (ref "R23") (pin "2") (pinfunction "2_2") (pintype "passive"))
      (node (ref "R26") (pin "1") (pinfunction "1_1") (pintype "passive"))
      (node (ref "U1") (pin "K10") (pinfunction "GPIO80_K10") (pintype "bidirectional"))
    )
    (net (code "39") (name "AP4_GP81{slash}VR-EN_USB3P3") (class "Default")
      (node (ref "U1") (pin "L10") (pinfunction "GPIO81_L10") (pintype "bidirectional"))
      (node (ref "VR4") (pin "3") (pinfunction "EN_3") (pintype "input"))
    )
    (net (code "40") (name "AP4_GP88{slash}LED2_YLW") (class "Default")
      (node (ref "R3") (pin "2") (pinfunction "2_2") (pintype "passive"))
      (node (ref "U1") (pin "F9") (pinfunction "GPIO88_F9") (pintype "bidirectional"))
    )
    (net (code "41") (name "AP4_SWDCLK") (class "Default")
      (node (ref "J1") (pin "4") (pinfunction "SWDCLK_4") (pintype "bidirectional"))
      (node (ref "J1") (pin "B4") (pinfunction "SWDCLK_B4") (pintype "bidirectional"))
      (node (ref "U1") (pin "K3") (pinfunction "GPIO20_K3") (pintype "bidirectional"))
    )
    (net (code "42") (name "AP4_SWDIO") (class "Default")
      (node (ref "J1") (pin "2") (pinfunction "SWDIO_2") (pintype "bidirectional"))
      (node (ref "J1") (pin "B2") (pinfunction "SWDIO_B2") (pintype "bidirectional"))
      (node (ref "U1") (pin "J3") (pinfunction "GPIO21_J3") (pintype "bidirectional"))
    )
    (net (code "43") (name "AP4_SWO") (class "Default")
      (node (ref "J1") (pin "6") (pinfunction "SWO_6") (pintype "bidirectional"))
      (node (ref "J1") (pin "B6") (pinfunction "SWO_B6") (pintype "bidirectional"))
      (node (ref "U1") (pin "L4") (pinfunction "GPIO3_L4") (pintype "bidirectional"))
    )
    (net (code "44") (name "AP4_USB0_N") (class "Default")
      (node (ref "D5") (pin "3") (pinfunction "I/O2_3") (pintype "bidirectional"))
      (node (ref "J7") (pin "A7") (pinfunction "DN1_A7") (pintype "bidirectional"))
      (node (ref "J7") (pin "B7") (pinfunction "DN2_B7") (pintype "bidirectional"))
      (node (ref "U1") (pin "M8") (pinfunction "USB0PN_M8") (pintype "bidirectional"))
    )
    (net (code "45") (name "AP4_USB0_P") (class "Default")
      (node (ref "D5") (pin "2") (pinfunction "I/O1_2") (pintype "bidirectional"))
      (node (ref "J7") (pin "A6") (pinfunction "DP1_A6") (pintype "bidirectional"))
      (node (ref "J7") (pin "B6") (pinfunction "DP2_B6") (pintype "bidirectional"))
      (node (ref "U1") (pin "M7") (pinfunction "USB0PP_M7") (pintype "bidirectional"))
    )
    (net (code "46") (name "AP4_VDDBH") (class "Default")
      (node (ref "C75") (pin "1") (pinfunction "1_1") (pintype "bidirectional"))
      (node (ref "L6") (pin "2") (pinfunction "2_2") (pintype "bidirectional"))
      (node (ref "RZ1") (pin "1") (pinfunction "1_1") (pintype "passive"))
      (node (ref "TP8") (pin "P$1") (pinfunction "TESTPOINT_P$1") (pintype "bidirectional"))
      (node (ref "U1") (pin "G12") (pinfunction "VDDBH--BLE_BUCK_VOUT_G12") (pintype "bidirectional"))
    )
    (net (code "47") (name "AP4_VDDBH_RF") (class "Default")
      (node (ref "C46") (pin "P$1") (pinfunction "1_P$1") (pintype "bidirectional"))
      (node (ref "RZ1") (pin "2") (pinfunction "2_2") (pintype "passive"))
      (node (ref "U1") (pin "J1") (pinfunction "VDDBH_RF--BLE_BUCK_RF_VOUT_J1") (pintype "bidirectional"))
    )
    (net (code "48") (name "AP4_VDDB_SUP") (class "Default")
      (node (ref "C72") (pin "P$1") (pinfunction "1_P$1") (pintype "bidirectional"))
      (node (ref "C73") (pin "P$1") (pinfunction "1_P$1") (pintype "bidirectional"))
      (node (ref "SJ8") (pin "2") (pinfunction "2_2") (pintype "passive"))
      (node (ref "U1") (pin "G1") (pinfunction "VDDB-BLE_SUPPLY_G1") (pintype "bidirectional"))
    )
    (net (code "49") (name "AP4_VDDF") (class "Default")
      (node (ref "C65") (pin "P$1") (pinfunction "1_P$1") (pintype "bidirectional"))
      (node (ref "C71") (pin "P$1") (pinfunction "1_P$1") (pintype "bidirectional"))
      (node (ref "TP10") (pin "P$1") (pinfunction "TESTPOINT_P$1") (pintype "bidirectional"))
      (node (ref "U1") (pin "C2") (pinfunction "VDDF-MEM_C2") (pintype "bidirectional"))
    )
    (net (code "50") (name "AP4_VDDMIPI_1P8") (class "Default")
      (node (ref "C66") (pin "P$1") (pinfunction "1_P$1") (pintype "bidirectional"))
      (node (ref "SJ7") (pin "1") (pinfunction "1_1") (pintype "passive"))
      (node (ref "U1") (pin "H10") (pinfunction "VDD18-MIPI_H10") (pintype "bidirectional"))
    )
    (net (code "51") (name "AP4_VDDUSB_0P9") (class "Default")
      (node (ref "C69") (pin "P$1") (pinfunction "1_P$1") (pintype "bidirectional"))
      (node (ref "SJ9") (pin "1") (pinfunction "1_1") (pintype "passive"))
      (node (ref "U1") (pin "L7") (pinfunction "VDDUSB0P9_L7") (pintype "bidirectional"))
    )
    (net (code "52") (name "AP4_VDDUSB_3P3") (class "Default")
      (node (ref "C70") (pin "P$1") (pinfunction "1_P$1") (pintype "bidirectional"))
      (node (ref "SJ10") (pin "1") (pinfunction "1_1") (pintype "passive"))
      (node (ref "U1") (pin "K7") (pinfunction "VDDUSB33_K7") (pintype "bidirectional"))
    )
    (net (code "53") (name "AP4_~{RESET}") (class "Default")
      (node (ref "C17") (pin "P$2") (pinfunction "P$2_P$2") (pintype "bidirectional"))
      (node (ref "D3") (pin "1") (pinfunction "C_1") (pintype "passive"))
      (node (ref "J1") (pin "3") (pinfunction "~{RESET}_3") (pintype "bidirectional"))
      (node (ref "J1") (pin "B3") (pinfunction "~{RESET}_B3") (pintype "bidirectional"))
      (node (ref "U1") (pin "A6") (pinfunction "~{RST}_A6") (pintype "input"))
    )
    (net (code "54") (name "BATT_THERM") (class "Default")
      (node (ref "J4") (pin "2") (pinfunction "2_2") (pintype "bidirectional"))
      (node (ref "J4") (pin "2SUPP") (pinfunction "2_2SUPP") (pintype "bidirectional"))
      (node (ref "SJ1") (pin "3") (pinfunction "3_3") (pintype "passive"))
    )
    (net (code "55") (name "BATT_TS") (class "Default")
      (node (ref "SJ1") (pin "2") (pinfunction "2_2") (pintype "passive"))
      (node (ref "U3") (pin "9") (pinfunction "TS_9") (pintype "bidirectional"))
    )
    (net (code "56") (name "BNO_ENV_SCL") (class "Default")
      (node (ref "R15") (pin "1") (pinfunction "1_1") (pintype "passive"))
      (node (ref "U6") (pin "15") (pinfunction "ENV_SCL_15") (pintype "bidirectional"))
    )
    (net (code "57") (name "BNO_ENV_SDA") (class "Default")
      (node (ref "R16") (pin "1") (pinfunction "1_1") (pintype "passive"))
      (node (ref "U6") (pin "16") (pinfunction "ENV_SDA_16") (pintype "bidirectional"))
    )
    (net (code "58") (name "DW_EXTON") (class "Default")
      (node (ref "S3") (pin "2") (pinfunction "CTL_2") (pintype "bidirectional"))
      (node (ref "S3") (pin "3") (pinfunction "CTL_3") (pintype "bidirectional"))
      (node (ref "SJ2") (pin "2") (pinfunction "2_2") (pintype "passive"))
      (node (ref "VR3") (pin "3") (pinfunction "EN_3") (pintype "input"))
    )
    (net (code "59") (name "DW_EXTON_RAW") (class "Default")
      (node (ref "SJ2") (pin "3") (pinfunction "3_3") (pintype "passive"))
      (node (ref "U2") (pin "A12") (pinfunction "EXTON_A12") (pintype "bidirectional"))
    )
    (net (code "60") (name "DW_GPIO6{slash}EXTRXE") (class "Default")
      (node (ref "SJ3") (pin "3") (pinfunction "3_3") (pintype "passive"))
      (node (ref "TP6") (pin "P$1") (pinfunction "TESTPOINT_P$1") (pintype "bidirectional"))
      (node (ref "U2") (pin "C4") (pinfunction "GPIO6/EXTRXE/SPIPHA_C4") (pintype "bidirectional"))
    )
    (net (code "61") (name "DW_RF1_BLKD") (class "Default")
      (node (ref "C2") (pin "P$2") (pinfunction "2_P$2") (pintype "bidirectional"))
      (node (ref "U7") (pin "6") (pinfunction "LNA_OUT_6") (pintype "bidirectional"))
    )
    (net (code "62") (name "DW_SYNC") (class "Default")
      (node (ref "TP7") (pin "P$1") (pinfunction "TESTPOINT_P$1") (pintype "bidirectional"))
      (node (ref "U2") (pin "G2") (pinfunction "GPIO7/SYNC_G2") (pintype "bidirectional"))
    )
    (net (code "63") (name "DW_VDD2_SUP") (class "Default")
      (node (ref "C15") (pin "P$1") (pinfunction "P$1_P$1") (pintype "bidirectional"))
      (node (ref "C28") (pin "P$1") (pinfunction "P$1_P$1") (pintype "bidirectional"))
      (node (ref "C86") (pin "P$1") (pinfunction "P$1_P$1") (pintype "bidirectional"))
      (node (ref "FB1") (pin "P$1") (pinfunction "P$1_P$1") (pintype "bidirectional"))
      (node (ref "RZ2") (pin "2") (pinfunction "2_2") (pintype "passive"))
      (node (ref "U2") (pin "B15") (pinfunction "VDD2B_B15") (pintype "bidirectional"))
    )
    (net (code "64") (name "DW_VDD3_SUP") (class "Default")
      (node (ref "C16") (pin "P$2") (pinfunction "P$2_P$2") (pintype "bidirectional"))
      (node (ref "C26") (pin "P$2") (pinfunction "P$2_P$2") (pintype "bidirectional"))
      (node (ref "C85") (pin "P$2") (pinfunction "P$2_P$2") (pintype "bidirectional"))
      (node (ref "RZ3") (pin "2") (pinfunction "2_2") (pintype "passive"))
      (node (ref "U2") (pin "D15") (pinfunction "VDD3_D15") (pintype "bidirectional"))
    )
    (net (code "65") (name "GND") (class "Default")
      (node (ref "C11") (pin "P$2") (pinfunction "P$2_P$2") (pintype "bidirectional"))
      (node (ref "C14") (pin "P$2") (pinfunction "P$2_P$2") (pintype "bidirectional"))
      (node (ref "C15") (pin "P$2") (pinfunction "P$2_P$2") (pintype "bidirectional"))
      (node (ref "C16") (pin "P$1") (pinfunction "P$1_P$1") (pintype "bidirectional"))
      (node (ref "C17") (pin "P$1") (pinfunction "P$1_P$1") (pintype "bidirectional"))
      (node (ref "C25") (pin "P$2") (pinfunction "P$2_P$2") (pintype "bidirectional"))
      (node (ref "C26") (pin "P$1") (pinfunction "P$1_P$1") (pintype "bidirectional"))
      (node (ref "C27") (pin "2") (pinfunction "2_2") (pintype "bidirectional"))
      (node (ref "C28") (pin "P$2") (pinfunction "P$2_P$2") (pintype "bidirectional"))
      (node (ref "C29") (pin "2") (pinfunction "2_2") (pintype "bidirectional"))
      (node (ref "C3") (pin "P$2") (pinfunction "P$2_P$2") (pintype "bidirectional"))
      (node (ref "C30") (pin "2") (pinfunction "2_2") (pintype "bidirectional"))
      (node (ref "C31") (pin "2") (pinfunction "2_2") (pintype "bidirectional"))
      (node (ref "C32") (pin "2") (pinfunction "2_2") (pintype "bidirectional"))
      (node (ref "C33") (pin "2") (pinfunction "2_2") (pintype "bidirectional"))
      (node (ref "C34") (pin "2") (pinfunction "2_2") (pintype "bidirectional"))
      (node (ref "C35") (pin "2") (pinfunction "2_2") (pintype "bidirectional"))
      (node (ref "C36") (pin "2") (pinfunction "2_2") (pintype "bidirectional"))
      (node (ref "C37") (pin "2") (pinfunction "2_2") (pintype "bidirectional"))
      (node (ref "C38") (pin "2") (pinfunction "2_2") (pintype "bidirectional"))
      (node (ref "C39") (pin "2") (pinfunction "2_2") (pintype "bidirectional"))
      (node (ref "C4") (pin "P$2") (pinfunction "P$2_P$2") (pintype "bidirectional"))
      (node (ref "C40") (pin "2") (pinfunction "2_2") (pintype "bidirectional"))
      (node (ref "C41") (pin "P$1") (pinfunction "P$1_P$1") (pintype "bidirectional"))
      (node (ref "C44") (pin "P$2") (pinfunction "2_P$2") (pintype "bidirectional"))
      (node (ref "C45") (pin "P$2") (pinfunction "2_P$2") (pintype "bidirectional"))
      (node (ref "C47") (pin "P$2") (pinfunction "2_P$2") (pintype "bidirectional"))
      (node (ref "C48") (pin "P$2") (pinfunction "2_P$2") (pintype "bidirectional"))
      (node (ref "C49") (pin "P$1") (pinfunction "1_P$1") (pintype "bidirectional"))
      (node (ref "C5") (pin "P$1") (pinfunction "1_P$1") (pintype "bidirectional"))
      (node (ref "C50") (pin "P$2") (pinfunction "2_P$2") (pintype "bidirectional"))
      (node (ref "C51") (pin "P$2") (pinfunction "2_P$2") (pintype "bidirectional"))
      (node (ref "C52") (pin "P$2") (pinfunction "2_P$2") (pintype "bidirectional"))
      (node (ref "C53") (pin "P$2") (pinfunction "2_P$2") (pintype "bidirectional"))
      (node (ref "C54") (pin "P$2") (pinfunction "2_P$2") (pintype "bidirectional"))
      (node (ref "C55") (pin "P$2") (pinfunction "2_P$2") (pintype "bidirectional"))
      (node (ref "C56") (pin "P$2") (pinfunction "2_P$2") (pintype "bidirectional"))
      (node (ref "C57") (pin "P$2") (pinfunction "2_P$2") (pintype "bidirectional"))
      (node (ref "C58") (pin "P$2") (pinfunction "2_P$2") (pintype "bidirectional"))
      (node (ref "C59") (pin "P$2") (pinfunction "2_P$2") (pintype "bidirectional"))
      (node (ref "C6") (pin "P$1") (pinfunction "1_P$1") (pintype "bidirectional"))
      (node (ref "C60") (pin "P$1") (pinfunction "1_P$1") (pintype "bidirectional"))
      (node (ref "C61") (pin "P$1") (pinfunction "1_P$1") (pintype "bidirectional"))
      (node (ref "C62") (pin "P$2") (pinfunction "2_P$2") (pintype "bidirectional"))
      (node (ref "C63") (pin "P$2") (pinfunction "2_P$2") (pintype "bidirectional"))
      (node (ref "C64") (pin "P$2") (pinfunction "2_P$2") (pintype "bidirectional"))
      (node (ref "C65") (pin "P$2") (pinfunction "2_P$2") (pintype "bidirectional"))
      (node (ref "C66") (pin "P$2") (pinfunction "2_P$2") (pintype "bidirectional"))
      (node (ref "C67") (pin "P$1") (pinfunction "1_P$1") (pintype "bidirectional"))
      (node (ref "C68") (pin "P$2") (pinfunction "2_P$2") (pintype "bidirectional"))
      (node (ref "C69") (pin "P$2") (pinfunction "2_P$2") (pintype "bidirectional"))
      (node (ref "C7") (pin "2") (pinfunction "2_2") (pintype "passive"))
      (node (ref "C70") (pin "P$2") (pinfunction "2_P$2") (pintype "bidirectional"))
      (node (ref "C72") (pin "P$2") (pinfunction "2_P$2") (pintype "bidirectional"))
      (node (ref "C73") (pin "P$2") (pinfunction "2_P$2") (pintype "bidirectional"))
      (node (ref "C74") (pin "P$2") (pinfunction "2_P$2") (pintype "bidirectional"))
      (node (ref "C75") (pin "2") (pinfunction "2_2") (pintype "bidirectional"))
      (node (ref "C76") (pin "1") (pinfunction "1_1") (pintype "bidirectional"))
      (node (ref "C77") (pin "2") (pinfunction "2_2") (pintype "bidirectional"))
      (node (ref "C78") (pin "1") (pinfunction "1_1") (pintype "bidirectional"))
      (node (ref "C79") (pin "2") (pinfunction "2_2") (pintype "bidirectional"))
      (node (ref "C8") (pin "2") (pinfunction "2_2") (pintype "passive"))
      (node (ref "C80") (pin "2") (pinfunction "2_2") (pintype "bidirectional"))
      (node (ref "C81") (pin "1") (pinfunction "1_1") (pintype "bidirectional"))
      (node (ref "C82") (pin "2") (pinfunction "2_2") (pintype "bidirectional"))
      (node (ref "C83") (pin "2") (pinfunction "2_2") (pintype "bidirectional"))
      (node (ref "C84") (pin "2") (pinfunction "2_2") (pintype "bidirectional"))
      (node (ref "C85") (pin "P$1") (pinfunction "P$1_P$1") (pintype "bidirectional"))
      (node (ref "C86") (pin "P$2") (pinfunction "P$2_P$2") (pintype "bidirectional"))
      (node (ref "CX1") (pin "2") (pinfunction "2_2") (pintype "passive"))
      (node (ref "CX2") (pin "2") (pinfunction "2_2") (pintype "passive"))
      (node (ref "D3") (pin "2") (pinfunction "A_2") (pintype "passive"))
      (node (ref "D5") (pin "1") (pinfunction "GND_1") (pintype "bidirectional"))
      (node (ref "J1") (pin "5") (pinfunction "GND_5") (pintype "bidirectional"))
      (node (ref "J1") (pin "B5") (pinfunction "GND_B5") (pintype "bidirectional"))
      (node (ref "J3") (pin "2") (pinfunction "2_2") (pintype "passive"))
      (node (ref "J4") (pin "1") (pinfunction "1_1") (pintype "bidirectional"))
      (node (ref "J4") (pin "1SUPP") (pinfunction "1_1SUPP") (pintype "bidirectional"))
      (node (ref "J7") (pin "A1/B12") (pinfunction "GND_A1/B12") (pintype "power_in"))
      (node (ref "J7") (pin "B1/A12") (pinfunction "GND_B1/A12") (pintype "power_in"))
      (node (ref "J7") (pin "S1") (pinfunction "GND_S1") (pintype "power_in"))
      (node (ref "J7") (pin "S2") (pinfunction "GND_S2") (pintype "power_in"))
      (node (ref "J7") (pin "S3") (pinfunction "GND_S3") (pintype "power_in"))
      (node (ref "J7") (pin "S4") (pinfunction "GND_S4") (pintype "power_in"))
      (node (ref "Q2") (pin "S") (pinfunction "S_S") (pintype "passive"))
      (node (ref "R1") (pin "2") (pinfunction "2_2") (pintype "passive"))
      (node (ref "R10") (pin "1") (pinfunction "1_1") (pintype "passive"))
      (node (ref "R11") (pin "1") (pinfunction "1_1") (pintype "passive"))
      (node (ref "R12") (pin "2") (pinfunction "2_2") (pintype "passive"))
      (node (ref "R13") (pin "2") (pinfunction "2_2") (pintype "passive"))
      (node (ref "R19") (pin "1") (pinfunction "1_1") (pintype "passive"))
      (node (ref "R20") (pin "2") (pinfunction "2_2") (pintype "passive"))
      (node (ref "R21") (pin "1") (pinfunction "1_1") (pintype "passive"))
      (node (ref "R22") (pin "1") (pinfunction "1_1") (pintype "passive"))
      (node (ref "R23") (pin "1") (pinfunction "1_1") (pintype "passive"))
      (node (ref "R27") (pin "1") (pinfunction "1_1") (pintype "passive"))
      (node (ref "R6") (pin "2") (pinfunction "2_2") (pintype "passive"))
      (node (ref "RX1") (pin "1") (pinfunction "1_1") (pintype "passive"))
      (node (ref "RX2") (pin "1") (pinfunction "1_1") (pintype "passive"))
      (node (ref "S2") (pin "10") (pinfunction "GND_10") (pintype "bidirectional"))
      (node (ref "S2") (pin "12") (pinfunction "GND_12") (pintype "bidirectional"))
      (node (ref "S2") (pin "2") (pinfunction "GND_2") (pintype "bidirectional"))
      (node (ref "S2") (pin "7") (pinfunction "GND_7") (pintype "bidirectional"))
      (node (ref "S2") (pin "8") (pinfunction "GND_8") (pintype "bidirectional"))
      (node (ref "S2") (pin "PAD") (pinfunction "GND_PAD") (pintype "bidirectional"))
      (node (ref "S3") (pin "6") (pinfunction "GND_6") (pintype "bidirectional"))
      (node (ref "S3") (pin "7") (pinfunction "GND_7") (pintype "bidirectional"))
      (node (ref "S3") (pin "PAD") (pinfunction "GND_PAD") (pintype "bidirectional"))
      (node (ref "SJ3") (pin "1") (pinfunction "1_1") (pintype "passive"))
      (node (ref "SJ4") (pin "1") (pinfunction "1_1") (pintype "passive"))
      (node (ref "SJ7") (pin "2") (pinfunction "2_2") (pintype "passive"))
      (node (ref "U1") (pin "B12") (pinfunction "VSSAUDA_B12") (pintype "bidirectional"))
      (node (ref "U1") (pin "B2") (pinfunction "VSSP-BUCK_REGS_GND_B2") (pintype "bidirectional"))
      (node (ref "U1") (pin "B5") (pinfunction "VSSA-ANALOG_GND_B5") (pintype "bidirectional"))
      (node (ref "U1") (pin "D2") (pinfunction "VSS-DGND_FOR_VDDF_AND_PADS_D2") (pintype "bidirectional"))
      (node (ref "U1") (pin "E12") (pinfunction "VSSAUDD_E12") (pintype "bidirectional"))
      (node (ref "U1") (pin "H1") (pinfunction "VSSB-BLE_UNREG_GND_H1") (pintype "bidirectional"))
      (node (ref "U1") (pin "J10") (pinfunction "VSS18-MIPI_J10") (pintype "bidirectional"))
      (node (ref "U1") (pin "L1") (pinfunction "VSSVCO-BLECORE_GND_FOR_VCO_L1") (pintype "bidirectional"))
      (node (ref "U1") (pin "L2") (pinfunction "VSSS-HVSIMOBUCK_GND_L2") (pintype "bidirectional"))
      (node (ref "U1") (pin "L8") (pinfunction "VSSAUSB_L8") (pintype "bidirectional"))
      (node (ref "U2") (pin "A14") (pinfunction "VSS1_A14") (pintype "bidirectional"))
      (node (ref "U2") (pin "A2") (pinfunction "VSS_A2") (pintype "bidirectional"))
      (node (ref "U2") (pin "B11") (pinfunction "VSS1_B11") (pintype "bidirectional"))
      (node (ref "U2") (pin "B3") (pinfunction "VSS_B3") (pintype "bidirectional"))
      (node (ref "U2") (pin "C10") (pinfunction "VSS1_C10") (pintype "bidirectional"))
      (node (ref "U2") (pin "C12") (pinfunction "VSS3_C12") (pintype "bidirectional"))
      (node (ref "U2") (pin "C6") (pinfunction "VSS_C6") (pintype "bidirectional"))
      (node (ref "U2") (pin "C8") (pinfunction "VSS1_C8") (pintype "bidirectional"))
      (node (ref "U2") (pin "D11") (pinfunction "VSS2_D11") (pintype "bidirectional"))
      (node (ref "U2") (pin "D13") (pinfunction "VSS3_D13") (pintype "bidirectional"))
      (node (ref "U2") (pin "D5") (pinfunction "VSS_D5") (pintype "bidirectional"))
      (node (ref "U2") (pin "D7") (pinfunction "VSS_D7") (pintype "bidirectional"))
      (node (ref "U2") (pin "D9") (pinfunction "VSS1_D9") (pintype "bidirectional"))
      (node (ref "U2") (pin "E10") (pinfunction "GND-RF_E10") (pintype "bidirectional"))
      (node (ref "U2") (pin "E12") (pinfunction "GND-RF_E12") (pintype "bidirectional"))
      (node (ref "U2") (pin "E14") (pinfunction "VSS2_E14") (pintype "bidirectional"))
      (node (ref "U2") (pin "E6") (pinfunction "GND-RF_E6") (pintype "bidirectional"))
      (node (ref "U2") (pin "F7") (pinfunction "GND-RF_F7") (pintype "bidirectional"))
      (node (ref "U2") (pin "F9") (pinfunction "GND-RF_F9") (pintype "bidirectional"))
      (node (ref "U2") (pin "G10") (pinfunction "GND-RF_G10") (pintype "bidirectional"))
      (node (ref "U2") (pin "G6") (pinfunction "GND-RF_G6") (pintype "bidirectional"))
      (node (ref "U2") (pin "H1") (pinfunction "GND-RF_H1") (pintype "bidirectional"))
      (node (ref "U2") (pin "H13") (pinfunction "GND-RF_H13") (pintype "bidirectional"))
      (node (ref "U2") (pin "H3") (pinfunction "GND-RF_H3") (pintype "bidirectional"))
      (node (ref "U2") (pin "H7") (pinfunction "GND-RF_H7") (pintype "bidirectional"))
      (node (ref "U2") (pin "H9") (pinfunction "GND-RF_H9") (pintype "bidirectional"))
      (node (ref "U3") (pin "3") (pinfunction "VSS_3") (pintype "bidirectional"))
      (node (ref "U3") (pin "7") (pinfunction "ISET2_7") (pintype "bidirectional"))
      (node (ref "U3") (pin "PAD") (pinfunction "VSS_PAD") (pintype "bidirectional"))
      (node (ref "U4") (pin "1") (pinfunction "PGND_1") (pintype "bidirectional"))
      (node (ref "U4") (pin "10") (pinfunction "EN1_10") (pintype "bidirectional"))
      (node (ref "U4") (pin "11") (pinfunction "EN2_11") (pintype "bidirectional"))
      (node (ref "U4") (pin "20") (pinfunction "PGND_20") (pintype "bidirectional"))
      (node (ref "U4") (pin "PAD") (pinfunction "PGND_PAD") (pintype "bidirectional"))
      (node (ref "U6") (pin "10") (pinfunction "CLKSEL0_10") (pintype "output"))
      (node (ref "U6") (pin "2") (pinfunction "GND_2") (pintype "bidirectional"))
      (node (ref "U6") (pin "25") (pinfunction "GNDIO_25") (pintype "bidirectional"))
      (node (ref "U7") (pin "3") (pinfunction "GND_3") (pintype "bidirectional"))
      (node (ref "U7") (pin "4") (pinfunction "GND_4") (pintype "bidirectional"))
      (node (ref "U7") (pin "5") (pinfunction "GND_5") (pintype "bidirectional"))
      (node (ref "U7") (pin "7") (pinfunction "GND_7") (pintype "bidirectional"))
      (node (ref "U7") (pin "9") (pinfunction "GND_9") (pintype "bidirectional"))
      (node (ref "U8") (pin "4") (pinfunction "GND_4") (pintype "bidirectional"))
      (node (ref "VR1") (pin "13") (pinfunction "GND2_13") (pintype "bidirectional"))
      (node (ref "VR1") (pin "3") (pinfunction "GND2_3") (pintype "bidirectional"))
      (node (ref "VR1") (pin "9") (pinfunction "GND1_9") (pintype "bidirectional"))
      (node (ref "VR2") (pin "2") (pinfunction "GND_2") (pintype "bidirectional"))
      (node (ref "VR2") (pin "PAD") (pinfunction "GND_PAD") (pintype "bidirectional"))
      (node (ref "VR3") (pin "2") (pinfunction "GND_2") (pintype "bidirectional"))
      (node (ref "VR3") (pin "PAD") (pinfunction "GND_PAD") (pintype "bidirectional"))
      (node (ref "VR4") (pin "2") (pinfunction "GND_2") (pintype "bidirectional"))
      (node (ref "VR4") (pin "PAD") (pinfunction "GND_PAD") (pintype "bidirectional"))
      (node (ref "VR5") (pin "2") (pinfunction "GND_2") (pintype "bidirectional"))
      (node (ref "X1") (pin "2") (pinfunction "GND_2") (pintype "bidirectional"))
      (node (ref "X1") (pin "4") (pinfunction "GND_4") (pintype "bidirectional"))
      (node (ref "X4") (pin "2") (pinfunction "GND_2") (pintype "bidirectional"))
      (node (ref "X4") (pin "4") (pinfunction "GND_4") (pintype "bidirectional"))
    )
    (net (code "66") (name "Net-(A4-ANTENNA)") (class "Default")
      (node (ref "A4") (pin "S1") (pinfunction "ANTENNA_S1") (pintype "bidirectional"))
      (node (ref "L8") (pin "2") (pinfunction "2_2") (pintype "passive"))
    )
    (net (code "67") (name "Net-(C1-Pad1)") (class "Default")
      (node (ref "C1") (pin "1") (pinfunction "1_1") (pintype "passive"))
      (node (ref "L7") (pin "2") (pinfunction "2_2") (pintype "passive"))
      (node (ref "L8") (pin "1") (pinfunction "1_1") (pintype "passive"))
    )
    (net (code "68") (name "Net-(C2-1)") (class "Default")
      (node (ref "C2") (pin "P$1") (pinfunction "1_P$1") (pintype "bidirectional"))
      (node (ref "U2") (pin "H11") (pinfunction "RF1_H11") (pintype "bidirectional"))
    )
    (net (code "69") (name "Net-(C5-2)") (class "Default")
      (node (ref "C5") (pin "P$2") (pinfunction "2_P$2") (pintype "bidirectional"))
      (node (ref "U6") (pin "27") (pinfunction "XIN32_27") (pintype "bidirectional"))
      (node (ref "X2") (pin "2") (pinfunction "2_2") (pintype "bidirectional"))
    )
    (net (code "70") (name "Net-(C6-2)") (class "Default")
      (node (ref "C6") (pin "P$2") (pinfunction "2_P$2") (pintype "bidirectional"))
      (node (ref "U6") (pin "26") (pinfunction "XOUT32/CLKSEL1_26") (pintype "bidirectional"))
      (node (ref "X2") (pin "1") (pinfunction "1_1") (pintype "bidirectional"))
    )
    (net (code "71") (name "Net-(C9-2)") (class "Default")
      (node (ref "C9") (pin "P$2") (pinfunction "2_P$2") (pintype "bidirectional"))
      (node (ref "R21") (pin "2") (pinfunction "2_2") (pintype "passive"))
      (node (ref "R24") (pin "1") (pinfunction "1_1") (pintype "passive"))
      (node (ref "VR1") (pin "10") (pinfunction "FB2_10") (pintype "bidirectional"))
    )
    (net (code "72") (name "Net-(C10-1)") (class "Default")
      (node (ref "C10") (pin "P$1") (pinfunction "1_P$1") (pintype "bidirectional"))
      (node (ref "R22") (pin "2") (pinfunction "2_2") (pintype "passive"))
      (node (ref "R25") (pin "2") (pinfunction "2_2") (pintype "passive"))
      (node (ref "VR1") (pin "4") (pinfunction "FB1_4") (pintype "bidirectional"))
    )
    (net (code "73") (name "Net-(C45-1)") (class "Default")
      (node (ref "C11") (pin "P$1") (pinfunction "P$1_P$1") (pintype "bidirectional"))
      (node (ref "C25") (pin "P$1") (pinfunction "P$1_P$1") (pintype "bidirectional"))
      (node (ref "C45") (pin "P$1") (pinfunction "1_P$1") (pintype "bidirectional"))
      (node (ref "U7") (pin "1") (pinfunction "VDD_1") (pintype "bidirectional"))
      (node (ref "VR3") (pin "1") (pinfunction "OUT_1") (pintype "power_in"))
    )
    (net (code "74") (name "Net-(C49-2)") (class "Default")
      (node (ref "C49") (pin "P$2") (pinfunction "2_P$2") (pintype "bidirectional"))
      (node (ref "U1") (pin "A12") (pinfunction "LPADC_VREF_A12") (pintype "bidirectional"))
    )
    (net (code "75") (name "Net-(C50-1)") (class "Default")
      (node (ref "C50") (pin "P$1") (pinfunction "1_P$1") (pintype "bidirectional"))
      (node (ref "SJ10") (pin "2") (pinfunction "2_2") (pintype "passive"))
      (node (ref "VR4") (pin "1") (pinfunction "OUT_1") (pintype "power_in"))
    )
    (net (code "76") (name "Net-(C52-1)") (class "Default")
      (node (ref "C52") (pin "P$1") (pinfunction "1_P$1") (pintype "bidirectional"))
      (node (ref "SJ9") (pin "2") (pinfunction "2_2") (pintype "passive"))
      (node (ref "VR5") (pin "5") (pinfunction "OUT_5") (pintype "power_in"))
    )
    (net (code "77") (name "Net-(C62-1)") (class "Default")
      (node (ref "C62") (pin "P$1") (pinfunction "1_P$1") (pintype "bidirectional"))
      (node (ref "U1") (pin "C1") (pinfunction "VDDS-SRAM_HV_SUP_C1") (pintype "bidirectional"))
    )
    (net (code "78") (name "Net-(C63-1)") (class "Default")
      (node (ref "C63") (pin "P$1") (pinfunction "1_P$1") (pintype "bidirectional"))
      (node (ref "U1") (pin "A3") (pinfunction "VDDC-CORE_A3") (pintype "bidirectional"))
    )
    (net (code "79") (name "Net-(C64-1)") (class "Default")
      (node (ref "C64") (pin "P$1") (pinfunction "1_P$1") (pintype "bidirectional"))
      (node (ref "U1") (pin "B3") (pinfunction "VDDC_LV-CORE_LV_B3") (pintype "bidirectional"))
    )
    (net (code "80") (name "Net-(C67-2)") (class "Default")
      (node (ref "C67") (pin "P$2") (pinfunction "2_P$2") (pintype "bidirectional"))
      (node (ref "U1") (pin "B10") (pinfunction "LPMICBIAS_B10") (pintype "output"))
    )
    (net (code "81") (name "Net-(D1-PadC1)") (class "Default")
      (node (ref "D1") (pin "C1") (pinfunction "C1_C1") (pintype "bidirectional"))
      (node (ref "R5") (pin "1") (pinfunction "1_1") (pintype "passive"))
    )
    (net (code "82") (name "Net-(D1-PadC2)") (class "Default")
      (node (ref "D1") (pin "C2") (pinfunction "C2_C2") (pintype "bidirectional"))
      (node (ref "R2") (pin "1") (pinfunction "1_1") (pintype "passive"))
    )
    (net (code "83") (name "Net-(D2-PadC1)") (class "Default")
      (node (ref "D2") (pin "C1") (pinfunction "C1_C1") (pintype "bidirectional"))
      (node (ref "R4") (pin "1") (pinfunction "1_1") (pintype "passive"))
    )
    (net (code "84") (name "Net-(D2-PadC2)") (class "Default")
      (node (ref "D2") (pin "C2") (pinfunction "C2_C2") (pintype "bidirectional"))
      (node (ref "R3") (pin "1") (pinfunction "1_1") (pintype "passive"))
    )
    (net (code "85") (name "Net-(J7-CC1)") (class "Default")
      (node (ref "J7") (pin "A5") (pinfunction "CC1_A5") (pintype "bidirectional"))
      (node (ref "R12") (pin "1") (pinfunction "1_1") (pintype "passive"))
    )
    (net (code "86") (name "Net-(J7-CC2)") (class "Default")
      (node (ref "J7") (pin "B5") (pinfunction "CC2_B5") (pintype "bidirectional"))
      (node (ref "R13") (pin "1") (pinfunction "1_1") (pintype "passive"))
    )
    (net (code "87") (name "Net-(L1-1)") (class "Default")
      (node (ref "L1") (pin "P$1") (pinfunction "1_P$1") (pintype "bidirectional"))
      (node (ref "VR1") (pin "2") (pinfunction "LX2_2") (pintype "bidirectional"))
    )
    (net (code "88") (name "Net-(L2-2)") (class "Default")
      (node (ref "L2") (pin "P$2") (pinfunction "2_P$2") (pintype "bidirectional"))
      (node (ref "VR1") (pin "8") (pinfunction "LX1_8") (pintype "bidirectional"))
    )
    (net (code "89") (name "Net-(L4-1)") (class "Default")
      (node (ref "C20") (pin "2") (pinfunction "2_2") (pintype "bidirectional"))
      (node (ref "C21") (pin "2") (pinfunction "2_2") (pintype "bidirectional"))
      (node (ref "C22") (pin "2") (pinfunction "2_2") (pintype "bidirectional"))
      (node (ref "L4") (pin "P$1") (pinfunction "1_P$1") (pintype "bidirectional"))
    )
    (net (code "90") (name "Net-(L4-2)") (class "Default")
      (node (ref "C12") (pin "2") (pinfunction "2_2") (pintype "bidirectional"))
      (node (ref "C13") (pin "2") (pinfunction "2_2") (pintype "bidirectional"))
      (node (ref "C19") (pin "2") (pinfunction "2_2") (pintype "bidirectional"))
      (node (ref "C24") (pin "2") (pinfunction "2_2") (pintype "bidirectional"))
      (node (ref "C43") (pin "2") (pinfunction "2_2") (pintype "bidirectional"))
      (node (ref "L4") (pin "P$2") (pinfunction "2_P$2") (pintype "bidirectional"))
      (node (ref "U4") (pin "19") (pinfunction "AC2_19") (pintype "bidirectional"))
    )
    (net (code "91") (name "Net-(L5-1)") (class "Default")
      (node (ref "L5") (pin "P$1") (pinfunction "1_P$1") (pintype "bidirectional"))
      (node (ref "U1") (pin "A1") (pinfunction "SIMOBUCK_SW_A1") (pintype "bidirectional"))
    )
    (net (code "92") (name "Net-(L5-2)") (class "Default")
      (node (ref "L5") (pin "P$2") (pinfunction "2_P$2") (pintype "bidirectional"))
      (node (ref "U1") (pin "A2") (pinfunction "SIMOBUCK_SWSEL_A2") (pintype "bidirectional"))
    )
    (net (code "93") (name "Net-(LS1-N)") (class "Default")
      (node (ref "D4") (pin "ANODE") (pinfunction "ANODE_ANODE") (pintype "bidirectional"))
      (node (ref "LS1") (pin "-") (pinfunction "N_-") (pintype "passive"))
      (node (ref "Q2") (pin "D") (pinfunction "D_D") (pintype "passive"))
    )
    (net (code "94") (name "Net-(R6-Pad1)") (class "Default")
      (node (ref "R6") (pin "1") (pinfunction "1_1") (pintype "passive"))
      (node (ref "R7") (pin "2") (pinfunction "2_2") (pintype "passive"))
    )
    (net (code "95") (name "Net-(R8-Pad2)") (class "Default")
      (node (ref "R8") (pin "2") (pinfunction "2_2") (pintype "passive"))
      (node (ref "R9") (pin "1") (pinfunction "1_1") (pintype "passive"))
    )
    (net (code "96") (name "Net-(R10-Pad2)") (class "Default")
      (node (ref "R10") (pin "2") (pinfunction "2_2") (pintype "passive"))
      (node (ref "RT1") (pin "1") (pinfunction "1_1") (pintype "passive"))
    )
    (net (code "97") (name "Net-(R17-Pad1)") (class "Default")
      (node (ref "R17") (pin "1") (pinfunction "1_1") (pintype "passive"))
      (node (ref "R18") (pin "2") (pinfunction "2_2") (pintype "passive"))
    )
    (net (code "98") (name "Net-(RX1-Pad2)") (class "Default")
      (node (ref "RX1") (pin "2") (pinfunction "2_2") (pintype "passive"))
      (node (ref "SJ1") (pin "1") (pinfunction "1_1") (pintype "passive"))
    )
    (net (code "99") (name "Net-(S3A-OUT)") (class "Default")
      (node (ref "C37") (pin "1") (pinfunction "1_1") (pintype "bidirectional"))
      (node (ref "RZ2") (pin "1") (pinfunction "1_1") (pintype "passive"))
      (node (ref "S3") (pin "8") (pinfunction "OUT_8") (pintype "bidirectional"))
    )
    (net (code "100") (name "Net-(S3B-OUT)") (class "Default")
      (node (ref "C29") (pin "1") (pinfunction "1_1") (pintype "bidirectional"))
      (node (ref "RZ3") (pin "1") (pinfunction "1_1") (pintype "passive"))
      (node (ref "S3") (pin "5") (pinfunction "OUT_5") (pintype "bidirectional"))
    )
    (net (code "101") (name "Net-(TP0-TESTPOINT)") (class "Default")
      (node (ref "TP0") (pin "P$1") (pinfunction "TESTPOINT_P$1") (pintype "bidirectional"))
      (node (ref "U2") (pin "C2") (pinfunction "GPIO0/RXOKLED_C2") (pintype "bidirectional"))
    )
    (net (code "102") (name "Net-(TP1-TESTPOINT)") (class "Default")
      (node (ref "TP1") (pin "P$1") (pinfunction "TESTPOINT_P$1") (pintype "bidirectional"))
      (node (ref "U2") (pin "D3") (pinfunction "GPIO1/SFDLED_D3") (pintype "bidirectional"))
    )
    (net (code "103") (name "Net-(TP2-TESTPOINT)") (class "Default")
      (node (ref "TP2") (pin "P$1") (pinfunction "TESTPOINT_P$1") (pintype "bidirectional"))
      (node (ref "U2") (pin "E4") (pinfunction "GPIO2/RXLED_E4") (pintype "bidirectional"))
    )
    (net (code "104") (name "Net-(TP3-TESTPOINT)") (class "Default")
      (node (ref "TP3") (pin "P$1") (pinfunction "TESTPOINT_P$1") (pintype "bidirectional"))
      (node (ref "U2") (pin "E2") (pinfunction "GPIO3/TXLED_E2") (pintype "bidirectional"))
    )
    (net (code "105") (name "Net-(TP4-TESTPOINT)") (class "Default")
      (node (ref "TP4") (pin "P$1") (pinfunction "TESTPOINT_P$1") (pintype "bidirectional"))
      (node (ref "U2") (pin "F1") (pinfunction "GPIO4/EXTPA_F1") (pintype "bidirectional"))
    )
    (net (code "106") (name "Net-(TP5-TESTPOINT)") (class "Default")
      (node (ref "TP5") (pin "P$1") (pinfunction "TESTPOINT_P$1") (pintype "bidirectional"))
      (node (ref "U2") (pin "D1") (pinfunction "GPIO5/EXTTXE/SPIPOL_D1") (pintype "bidirectional"))
    )
    (net (code "107") (name "Net-(U1-RFIOP)") (class "Default")
      (node (ref "L7") (pin "1") (pinfunction "1_1") (pintype "passive"))
      (node (ref "U1") (pin "M2") (pinfunction "RFIOP_M2") (pintype "bidirectional"))
    )
    (net (code "108") (name "Net-(U1-VDDBH_SW--BLE_BUCK_SW)") (class "Default")
      (node (ref "L6") (pin "1") (pinfunction "1_1") (pintype "bidirectional"))
      (node (ref "U1") (pin "H12") (pinfunction "VDDBH_SW--BLE_BUCK_SW_H12") (pintype "bidirectional"))
    )
    (net (code "109") (name "Net-(U1-XI)") (class "Default")
      (node (ref "C8") (pin "1") (pinfunction "1_1") (pintype "passive"))
      (node (ref "U1") (pin "A4") (pinfunction "XI_A4") (pintype "bidirectional"))
      (node (ref "X3") (pin "2") (pinfunction "2_2") (pintype "bidirectional"))
    )
    (net (code "110") (name "Net-(U1-XI32M)") (class "Default")
      (node (ref "CX2") (pin "1") (pinfunction "1_1") (pintype "passive"))
      (node (ref "U1") (pin "C12") (pinfunction "XI32M_C12") (pintype "bidirectional"))
      (node (ref "X1") (pin "3") (pinfunction "2_3") (pintype "bidirectional"))
    )
    (net (code "111") (name "Net-(U1-XO)") (class "Default")
      (node (ref "C7") (pin "1") (pinfunction "1_1") (pintype "passive"))
      (node (ref "U1") (pin "A5") (pinfunction "XO_A5") (pintype "bidirectional"))
      (node (ref "X3") (pin "1") (pinfunction "1_1") (pintype "bidirectional"))
    )
    (net (code "112") (name "Net-(U1-XO32M)") (class "Default")
      (node (ref "CX1") (pin "1") (pinfunction "1_1") (pintype "passive"))
      (node (ref "U1") (pin "D12") (pinfunction "XO32M_D12") (pintype "bidirectional"))
      (node (ref "X1") (pin "1") (pinfunction "1_1") (pintype "bidirectional"))
    )
    (net (code "113") (name "Net-(U2-RF2)") (class "Default")
      (node (ref "R1") (pin "1") (pinfunction "1_1") (pintype "passive"))
      (node (ref "U2") (pin "H5") (pinfunction "RF2_H5") (pintype "bidirectional"))
    )
    (net (code "114") (name "Net-(U2-VDD2A)") (class "Default")
      (node (ref "C14") (pin "P$1") (pinfunction "P$1_P$1") (pintype "bidirectional"))
      (node (ref "FB1") (pin "P$2") (pinfunction "P$2_P$2") (pintype "bidirectional"))
      (node (ref "U2") (pin "F15") (pinfunction "VDD2A_F15") (pintype "bidirectional"))
    )
    (net (code "115") (name "Net-(U2-VIO_D)") (class "Default")
      (node (ref "C27") (pin "1") (pinfunction "1_1") (pintype "bidirectional"))
      (node (ref "U2") (pin "A4") (pinfunction "VIO_D_A4") (pintype "bidirectional"))
    )
    (net (code "116") (name "Net-(U2-VTX_D)") (class "Default")
      (node (ref "C41") (pin "P$2") (pinfunction "P$2_P$2") (pintype "bidirectional"))
      (node (ref "U2") (pin "C14") (pinfunction "VTX_D_C14") (pintype "bidirectional"))
    )
    (net (code "117") (name "Net-(U2-XTI)") (class "Default")
      (node (ref "C3") (pin "P$1") (pinfunction "P$1_P$1") (pintype "bidirectional"))
      (node (ref "U2") (pin "H15") (pinfunction "XTI_H15") (pintype "bidirectional"))
      (node (ref "X4") (pin "1") (pinfunction "1_1") (pintype "bidirectional"))
    )
    (net (code "118") (name "Net-(U2-XTO)") (class "Default")
      (node (ref "C4") (pin "P$1") (pinfunction "P$1_P$1") (pintype "bidirectional"))
      (node (ref "U2") (pin "G14") (pinfunction "XTO_G14") (pintype "bidirectional"))
      (node (ref "X4") (pin "3") (pinfunction "2_3") (pintype "bidirectional"))
    )
    (net (code "119") (name "Net-(U3-ISET)") (class "Default")
      (node (ref "R11") (pin "2") (pinfunction "2_2") (pintype "passive"))
      (node (ref "U3") (pin "2") (pinfunction "ISET_2") (pintype "bidirectional"))
    )
    (net (code "120") (name "Net-(U3-PRETERM)") (class "Default")
      (node (ref "RX2") (pin "2") (pinfunction "2_2") (pintype "passive"))
      (node (ref "U3") (pin "4") (pinfunction "PRETERM_4") (pintype "bidirectional"))
    )
    (net (code "121") (name "Net-(U4-AC1)") (class "Default")
      (node (ref "C12") (pin "1") (pinfunction "1_1") (pintype "bidirectional"))
      (node (ref "C13") (pin "1") (pinfunction "1_1") (pintype "bidirectional"))
      (node (ref "C18") (pin "2") (pinfunction "2_2") (pintype "bidirectional"))
      (node (ref "C20") (pin "1") (pinfunction "1_1") (pintype "bidirectional"))
      (node (ref "C21") (pin "1") (pinfunction "1_1") (pintype "bidirectional"))
      (node (ref "C22") (pin "1") (pinfunction "1_1") (pintype "bidirectional"))
      (node (ref "C23") (pin "2") (pinfunction "2_2") (pintype "bidirectional"))
      (node (ref "C42") (pin "2") (pinfunction "2_2") (pintype "bidirectional"))
      (node (ref "U4") (pin "2") (pinfunction "AC1_2") (pintype "bidirectional"))
    )
    (net (code "122") (name "Net-(U4-BOOT1)") (class "Default")
      (node (ref "C18") (pin "1") (pinfunction "1_1") (pintype "bidirectional"))
      (node (ref "U4") (pin "3") (pinfunction "BOOT1_3") (pintype "bidirectional"))
    )
    (net (code "123") (name "Net-(U4-BOOT2)") (class "Default")
      (node (ref "C19") (pin "1") (pinfunction "1_1") (pintype "bidirectional"))
      (node (ref "U4") (pin "17") (pinfunction "BOOT2_17") (pintype "bidirectional"))
    )
    (net (code "124") (name "Net-(U4-CLAMP1)") (class "Default")
      (node (ref "C42") (pin "1") (pinfunction "1_1") (pintype "bidirectional"))
      (node (ref "U4") (pin "5") (pinfunction "CLAMP1_5") (pintype "bidirectional"))
    )
    (net (code "125") (name "Net-(U4-CLAMP2)") (class "Default")
      (node (ref "C43") (pin "1") (pinfunction "1_1") (pintype "bidirectional"))
      (node (ref "U4") (pin "16") (pinfunction "CLAMP2_16") (pintype "bidirectional"))
    )
    (net (code "126") (name "Net-(U4-COMM1)") (class "Default")
      (node (ref "C23") (pin "1") (pinfunction "1_1") (pintype "bidirectional"))
      (node (ref "U4") (pin "6") (pinfunction "COMM1_6") (pintype "bidirectional"))
    )
    (net (code "127") (name "Net-(U4-COMM2)") (class "Default")
      (node (ref "C24") (pin "1") (pinfunction "1_1") (pintype "bidirectional"))
      (node (ref "U4") (pin "15") (pinfunction "COMM2_15") (pintype "bidirectional"))
    )
    (net (code "128") (name "Net-(U4-FOD)") (class "Default")
      (node (ref "R17") (pin "2") (pinfunction "2_2") (pintype "passive"))
      (node (ref "R7") (pin "1") (pinfunction "1_1") (pintype "passive"))
      (node (ref "R9") (pin "2") (pinfunction "2_2") (pintype "passive"))
      (node (ref "U4") (pin "14") (pinfunction "FOD_14") (pintype "bidirectional"))
    )
    (net (code "129") (name "Net-(U4-ILIM)") (class "Default")
      (node (ref "R8") (pin "1") (pinfunction "1_1") (pintype "passive"))
      (node (ref "U4") (pin "12") (pinfunction "ILIM_12") (pintype "bidirectional"))
    )
    (net (code "130") (name "Net-(U4-RECT)") (class "Default")
      (node (ref "C32") (pin "1") (pinfunction "1_1") (pintype "bidirectional"))
      (node (ref "C83") (pin "1") (pinfunction "1_1") (pintype "bidirectional"))
      (node (ref "C84") (pin "1") (pinfunction "1_1") (pintype "bidirectional"))
      (node (ref "R18") (pin "1") (pinfunction "1_1") (pintype "passive"))
      (node (ref "U4") (pin "18") (pinfunction "RECT_18") (pintype "bidirectional"))
    )
    (net (code "131") (name "Net-(U6-CAP)") (class "Default")
      (node (ref "C40") (pin "1") (pinfunction "1_1") (pintype "bidirectional"))
      (node (ref "U6") (pin "9") (pinfunction "CAP_9") (pintype "bidirectional"))
    )
    (net (code "132") (name "Net-(U6-PS1)") (class "Default")
      (node (ref "SJ4") (pin "2") (pinfunction "2_2") (pintype "passive"))
      (node (ref "U6") (pin "5") (pinfunction "PS1_5") (pintype "input"))
    )
    (net (code "133") (name "Net-(U7-VCTRL)") (class "Default")
      (node (ref "SJ3") (pin "2") (pinfunction "2_2") (pintype "passive"))
      (node (ref "U7") (pin "8") (pinfunction "VCTRL_8") (pintype "bidirectional"))
    )
    (net (code "134") (name "RF1") (class "Default")
      (node (ref "A1") (pin "FEED") (pinfunction "ANTENNA_FEED") (pintype "bidirectional"))
      (node (ref "S2") (pin "9") (pinfunction "J2_9") (pintype "bidirectional"))
    )
    (net (code "135") (name "RF2") (class "Default")
      (node (ref "A2") (pin "FEED") (pinfunction "ANTENNA_FEED") (pintype "bidirectional"))
      (node (ref "S2") (pin "3") (pinfunction "J3_3") (pintype "bidirectional"))
    )
    (net (code "136") (name "RF3") (class "Default")
      (node (ref "A3") (pin "FEED") (pinfunction "ANTENNA_FEED") (pintype "bidirectional"))
      (node (ref "S2") (pin "1") (pinfunction "J1_1") (pintype "bidirectional"))
    )
    (net (code "137") (name "RFC") (class "Default")
      (node (ref "S2") (pin "11") (pinfunction "RFC_11") (pintype "bidirectional"))
      (node (ref "U7") (pin "2") (pinfunction "LNA_IN_2") (pintype "bidirectional"))
    )
    (net (code "138") (name "VBAT") (class "Default")
      (node (ref "C61") (pin "P$2") (pinfunction "2_P$2") (pintype "bidirectional"))
      (node (ref "J3") (pin "1") (pinfunction "1_1") (pintype "passive"))
      (node (ref "J4") (pin "3") (pinfunction "3_3") (pintype "bidirectional"))
      (node (ref "J4") (pin "3SUPP") (pinfunction "3_3SUPP") (pintype "bidirectional"))
      (node (ref "S1") (pin "2") (pinfunction "2_2") (pintype "passive"))
      (node (ref "U3") (pin "10") (pinfunction "OUT_10") (pintype "bidirectional"))
    )
    (net (code "139") (name "VBAT_SWITCHED") (class "Default")
      (node (ref "C51") (pin "P$1") (pinfunction "1_P$1") (pintype "bidirectional"))
      (node (ref "C57") (pin "P$1") (pinfunction "1_P$1") (pintype "bidirectional"))
      (node (ref "C76") (pin "2") (pinfunction "2_2") (pintype "bidirectional"))
      (node (ref "C79") (pin "1") (pinfunction "1_1") (pintype "bidirectional"))
      (node (ref "R28") (pin "2") (pinfunction "2_2") (pintype "passive"))
      (node (ref "R29") (pin "1") (pinfunction "1_1") (pintype "passive"))
      (node (ref "R30") (pin "1") (pinfunction "1_1") (pintype "passive"))
      (node (ref "S1") (pin "3") (pinfunction "3_3") (pintype "passive"))
      (node (ref "VR1") (pin "1") (pinfunction "VIN2_1") (pintype "bidirectional"))
      (node (ref "VR1") (pin "7") (pinfunction "VIN1_7") (pintype "bidirectional"))
      (node (ref "VR4") (pin "4") (pinfunction "IN_4") (pintype "bidirectional"))
      (node (ref "VR5") (pin "1") (pinfunction "IN_1") (pintype "bidirectional"))
    )
    (net (code "140") (name "VDDAUDA_1P8-CLEAN") (class "Default")
      (node (ref "C48") (pin "P$1") (pinfunction "1_P$1") (pintype "bidirectional"))
      (node (ref "C68") (pin "P$1") (pinfunction "1_P$1") (pintype "bidirectional"))
      (node (ref "U1") (pin "B11") (pinfunction "VDDAUDA_B11") (pintype "bidirectional"))
      (node (ref "VR2") (pin "1") (pinfunction "OUT_1") (pintype "power_in"))
    )
    (net (code "141") (name "VQI") (class "Default")
      (node (ref "C33") (pin "1") (pinfunction "1_1") (pintype "bidirectional"))
      (node (ref "C60") (pin "P$2") (pinfunction "2_P$2") (pintype "bidirectional"))
      (node (ref "C82") (pin "1") (pinfunction "1_1") (pintype "bidirectional"))
      (node (ref "Q1") (pin "A2") (pinfunction "D1_A2") (pintype "bidirectional"))
      (node (ref "Q1") (pin "A3") (pinfunction "D1_A3") (pintype "bidirectional"))
      (node (ref "Q1") (pin "B3") (pinfunction "D1_B3") (pintype "bidirectional"))
      (node (ref "U3") (pin "1") (pinfunction "IN_1") (pintype "bidirectional"))
      (node (ref "U4") (pin "4") (pinfunction "OUT_4") (pintype "bidirectional"))
    )
    (net (code "142") (name "VR1_1P8_EN") (class "Default")
      (node (ref "R30") (pin "2") (pinfunction "2_2") (pintype "passive"))
      (node (ref "VR1") (pin "6") (pinfunction "EN1_6") (pintype "bidirectional"))
    )
    (net (code "143") (name "VR1_2P5_EN") (class "Default")
      (node (ref "R29") (pin "2") (pinfunction "2_2") (pintype "passive"))
      (node (ref "VR1") (pin "12") (pinfunction "EN2_12") (pintype "bidirectional"))
    )
    (net (code "144") (name "VUSB") (class "Default")
      (node (ref "C59") (pin "P$1") (pinfunction "1_P$1") (pintype "bidirectional"))
      (node (ref "D5") (pin "4") (pinfunction "VCC_4") (pintype "bidirectional"))
      (node (ref "J7") (pin "A4/B9") (pinfunction "VBUS_A4/B9") (pintype "power_in"))
      (node (ref "J7") (pin "B4/A9") (pinfunction "VBUS_B4/A9") (pintype "power_in"))
      (node (ref "Q1") (pin "B2") (pinfunction "D2_B2") (pintype "bidirectional"))
      (node (ref "Q1") (pin "C2") (pinfunction "D2_C2") (pintype "bidirectional"))
      (node (ref "Q1") (pin "C3") (pinfunction "D2_C3") (pintype "bidirectional"))
      (node (ref "R26") (pin "2") (pinfunction "2_2") (pintype "passive"))
      (node (ref "U4") (pin "9") (pinfunction "AD_9") (pintype "bidirectional"))
    )
    (net (code "145") (name "unconnected-(J7-SBU1-PadA8)") (class "Default")
      (node (ref "J7") (pin "A8") (pinfunction "SBU1_A8") (pintype "bidirectional"))
    )
    (net (code "146") (name "unconnected-(J7-SBU2-PadB8)") (class "Default")
      (node (ref "J7") (pin "B8") (pinfunction "SBU2_B8") (pintype "bidirectional"))
    )
    (net (code "147") (name "unconnected-(Q1-S-PadB1)") (class "Default")
      (node (ref "Q1") (pin "B1") (pinfunction "S_B1") (pintype "bidirectional"))
    )
    (net (code "148") (name "unconnected-(S1-Pad1)") (class "Default")
      (node (ref "S1") (pin "1") (pinfunction "1_1") (pintype "passive"))
    )
    (net (code "149") (name "unconnected-(U1-GPIO0-PadH3)") (class "Default")
      (node (ref "U1") (pin "H3") (pinfunction "GPIO0_H3") (pintype "bidirectional"))
    )
    (net (code "150") (name "unconnected-(U1-GPIO1-PadJ4)") (class "Default")
      (node (ref "U1") (pin "J4") (pinfunction "GPIO1_J4") (pintype "bidirectional"))
    )
    (net (code "151") (name "unconnected-(U1-GPIO2-PadK4)") (class "Default")
      (node (ref "U1") (pin "K4") (pinfunction "GPIO2_K4") (pintype "bidirectional"))
    )
    (net (code "152") (name "unconnected-(U1-GPIO4-PadM4)") (class "Default")
      (node (ref "U1") (pin "M4") (pinfunction "GPIO4_M4") (pintype "bidirectional"))
    )
    (net (code "153") (name "unconnected-(U1-GPIO5-PadH4)") (class "Default")
      (node (ref "U1") (pin "H4") (pinfunction "GPIO5_H4") (pintype "bidirectional"))
    )
    (net (code "154") (name "unconnected-(U1-GPIO7-PadJ6)") (class "Default")
      (node (ref "U1") (pin "J6") (pinfunction "GPIO7_J6") (pintype "bidirectional"))
    )
    (net (code "155") (name "unconnected-(U1-GPIO11-PadE4)") (class "Default")
      (node (ref "U1") (pin "E4") (pinfunction "GPIO11_E4") (pintype "bidirectional"))
    )
    (net (code "156") (name "unconnected-(U1-GPIO12-PadB4)") (class "Default")
      (node (ref "U1") (pin "B4") (pinfunction "GPIO12_B4") (pintype "bidirectional"))
    )
    (net (code "157") (name "unconnected-(U1-GPIO15-PadE5)") (class "Default")
      (node (ref "U1") (pin "E5") (pinfunction "GPIO15_E5") (pintype "bidirectional"))
    )
    (net (code "158") (name "unconnected-(U1-GPIO16-PadD7)") (class "Default")
      (node (ref "U1") (pin "D7") (pinfunction "GPIO16_D7") (pintype "bidirectional"))
    )
    (net (code "159") (name "unconnected-(U1-GPIO19-PadC3)") (class "Default")
      (node (ref "U1") (pin "C3") (pinfunction "GPIO19_C3") (pintype "bidirectional"))
    )
    (net (code "160") (name "unconnected-(U1-GPIO22-PadF3)") (class "Default")
      (node (ref "U1") (pin "F3") (pinfunction "GPIO22_F3") (pintype "bidirectional"))
    )
    (net (code "161") (name "unconnected-(U1-GPIO23-PadF2)") (class "Default")
      (node (ref "U1") (pin "F2") (pinfunction "GPIO23_F2") (pintype "bidirectional"))
    )
    (net (code "162") (name "unconnected-(U1-GPIO28-PadE3)") (class "Default")
      (node (ref "U1") (pin "E3") (pinfunction "GPIO28_E3") (pintype "bidirectional"))
    )
    (net (code "163") (name "unconnected-(U1-GPIO29-PadF4)") (class "Default")
      (node (ref "U1") (pin "F4") (pinfunction "GPIO29_F4") (pintype "bidirectional"))
    )
    (net (code "164") (name "unconnected-(U1-GPIO37-PadF11)") (class "Default")
      (node (ref "U1") (pin "F11") (pinfunction "GPIO37_F11") (pintype "bidirectional"))
    )
    (net (code "165") (name "unconnected-(U1-GPIO38-PadF12)") (class "Default")
      (node (ref "U1") (pin "F12") (pinfunction "GPIO38_F12") (pintype "bidirectional"))
    )
    (net (code "166") (name "unconnected-(U1-GPIO52-PadC10)") (class "Default")
      (node (ref "U1") (pin "C10") (pinfunction "GPIO52_C10") (pintype "bidirectional"))
    )
    (net (code "167") (name "unconnected-(U1-GPIO54-PadD10)") (class "Default")
      (node (ref "U1") (pin "D10") (pinfunction "GPIO54_D10") (pintype "bidirectional"))
    )
    (net (code "168") (name "unconnected-(U1-GPIO56-PadE10)") (class "Default")
      (node (ref "U1") (pin "E10") (pinfunction "GPIO56_E10") (pintype "bidirectional"))
    )
    (net (code "169") (name "unconnected-(U1-GPIO57-PadE9)") (class "Default")
      (node (ref "U1") (pin "E9") (pinfunction "GPIO57_E9") (pintype "bidirectional"))
    )
    (net (code "170") (name "unconnected-(U1-GPIO59-PadJ8)") (class "Default")
      (node (ref "U1") (pin "J8") (pinfunction "GPIO59_J8") (pintype "bidirectional"))
    )
    (net (code "171") (name "unconnected-(U1-GPIO61-PadK6)") (class "Default")
      (node (ref "U1") (pin "K6") (pinfunction "GPIO61_K6") (pintype "bidirectional"))
    )
    (net (code "172") (name "unconnected-(U1-GPIO62-PadL6)") (class "Default")
      (node (ref "U1") (pin "L6") (pinfunction "GPIO62_L6") (pintype "bidirectional"))
    )
    (net (code "173") (name "unconnected-(U1-GPIO64-PadB6)") (class "Default")
      (node (ref "U1") (pin "B6") (pinfunction "GPIO64_B6") (pintype "bidirectional"))
    )
    (net (code "174") (name "unconnected-(U1-GPIO67-PadC6)") (class "Default")
      (node (ref "U1") (pin "C6") (pinfunction "GPIO67_C6") (pintype "bidirectional"))
    )
    (net (code "175") (name "unconnected-(U1-GPIO68-PadB7)") (class "Default")
      (node (ref "U1") (pin "B7") (pinfunction "GPIO68_B7") (pintype "bidirectional"))
    )
    (net (code "176") (name "unconnected-(U1-GPIO70-PadC5)") (class "Default")
      (node (ref "U1") (pin "C5") (pinfunction "GPIO70_C5") (pintype "bidirectional"))
    )
    (net (code "177") (name "unconnected-(U1-GPIO71-PadC7)") (class "Default")
      (node (ref "U1") (pin "C7") (pinfunction "GPIO71_C7") (pintype "bidirectional"))
    )
    (net (code "178") (name "unconnected-(U1-GPIO73-PadD8)") (class "Default")
      (node (ref "U1") (pin "D8") (pinfunction "GPIO73_D8") (pintype "bidirectional"))
    )
    (net (code "179") (name "unconnected-(U1-GPIO74-PadG11)") (class "Default")
      (node (ref "U1") (pin "G11") (pinfunction "GPIO74_G11") (pintype "bidirectional"))
    )
    (net (code "180") (name "unconnected-(U1-GPIO75-PadH11)") (class "Default")
      (node (ref "U1") (pin "H11") (pinfunction "GPIO75_H11") (pintype "bidirectional"))
    )
    (net (code "181") (name "unconnected-(U1-GPIO76-PadJ11)") (class "Default")
      (node (ref "U1") (pin "J11") (pinfunction "GPIO76_J11") (pintype "bidirectional"))
    )
    (net (code "182") (name "unconnected-(U1-GPIO77-PadK11)") (class "Default")
      (node (ref "U1") (pin "K11") (pinfunction "GPIO77_K11") (pintype "bidirectional"))
    )
    (net (code "183") (name "unconnected-(U1-GPIO82-PadL9)") (class "Default")
      (node (ref "U1") (pin "L9") (pinfunction "GPIO82_L9") (pintype "bidirectional"))
    )
    (net (code "184") (name "unconnected-(U1-GPIO83-PadK9)") (class "Default")
      (node (ref "U1") (pin "K9") (pinfunction "GPIO83_K9") (pintype "bidirectional"))
    )
    (net (code "185") (name "unconnected-(U1-GPIO84-PadJ9)") (class "Default")
      (node (ref "U1") (pin "J9") (pinfunction "GPIO84_J9") (pintype "bidirectional"))
    )
    (net (code "186") (name "unconnected-(U1-GPIO85-PadH9)") (class "Default")
      (node (ref "U1") (pin "H9") (pinfunction "GPIO85_H9") (pintype "bidirectional"))
    )
    (net (code "187") (name "unconnected-(U1-GPIO86-PadG10)") (class "Default")
      (node (ref "U1") (pin "G10") (pinfunction "GPIO86_G10") (pintype "bidirectional"))
    )
    (net (code "188") (name "unconnected-(U1-GPIO87-PadG9)") (class "Default")
      (node (ref "U1") (pin "G9") (pinfunction "GPIO87_G9") (pintype "bidirectional"))
    )
    (net (code "189") (name "unconnected-(U1-GPIO89-PadF10)") (class "Default")
      (node (ref "U1") (pin "F10") (pinfunction "GPIO89_F10") (pintype "bidirectional"))
    )
    (net (code "190") (name "unconnected-(U1-GPIO90-PadJ2)") (class "Default")
      (node (ref "U1") (pin "J2") (pinfunction "GPIO90_J2") (pintype "bidirectional"))
    )
    (net (code "191") (name "unconnected-(U1-GPIO91-PadK2)") (class "Default")
      (node (ref "U1") (pin "K2") (pinfunction "GPIO91_K2") (pintype "bidirectional"))
    )
    (net (code "192") (name "unconnected-(U1-LPADC_D0NSE0-PadA10)") (class "Default")
      (node (ref "U1") (pin "A10") (pinfunction "LPADC_D0NSE0_A10") (pintype "input"))
    )
    (net (code "193") (name "unconnected-(U1-LPADC_D0PSE1-PadA11)") (class "Default")
      (node (ref "U1") (pin "A11") (pinfunction "LPADC_D0PSE1_A11") (pintype "input"))
    )
    (net (code "194") (name "unconnected-(U1-LPADC_D1NSE2-PadC11)") (class "Default")
      (node (ref "U1") (pin "C11") (pinfunction "LPADC_D1NSE2_C11") (pintype "input"))
    )
    (net (code "195") (name "unconnected-(U1-LPADC_D1PSE3-PadD11)") (class "Default")
      (node (ref "U1") (pin "D11") (pinfunction "LPADC_D1PSE3_D11") (pintype "input"))
    )
    (net (code "196") (name "unconnected-(U1-MIPI_CLKN-PadJ12)") (class "Default")
      (node (ref "U1") (pin "J12") (pinfunction "MIPI_CLKN_J12") (pintype "bidirectional"))
    )
    (net (code "197") (name "unconnected-(U1-MIPI_CLKP-PadK12)") (class "Default")
      (node (ref "U1") (pin "K12") (pinfunction "MIPI_CLKP_K12") (pintype "bidirectional"))
    )
    (net (code "198") (name "unconnected-(U1-MIPI_DON-PadL12)") (class "Default")
      (node (ref "U1") (pin "L12") (pinfunction "MIPI_DON_L12") (pintype "bidirectional"))
    )
    (net (code "199") (name "unconnected-(U1-MIPI_DOP-PadM12)") (class "Default")
      (node (ref "U1") (pin "M12") (pinfunction "MIPI_DOP_M12") (pintype "bidirectional"))
    )
    (net (code "200") (name "unconnected-(U1-TXEN-PadK1)") (class "Default")
      (node (ref "U1") (pin "K1") (pinfunction "TXEN_K1") (pintype "output"))
    )
    (net (code "201") (name "unconnected-(VR1-NC1-Pad5)") (class "Default")
      (node (ref "VR1") (pin "5") (pinfunction "NC1_5") (pintype "bidirectional"))
    )
    (net (code "202") (name "unconnected-(VR1-NC2-Pad11)") (class "Default")
      (node (ref "VR1") (pin "11") (pinfunction "NC2_11") (pintype "bidirectional"))
    )
    (net (code "203") (name "~{AD_EN}") (class "Default")
      (node (ref "Q1") (pin "A1") (pinfunction "G1_A1") (pintype "input"))
      (node (ref "Q1") (pin "C1") (pinfunction "G2_C1") (pintype "input"))
      (node (ref "U4") (pin "8") (pinfunction "~{AD-EN}_8") (pintype "bidirectional"))
    )
  )
)
